# ShiftReg.net
KiCad netlist of a schematic drawn in EAGLE
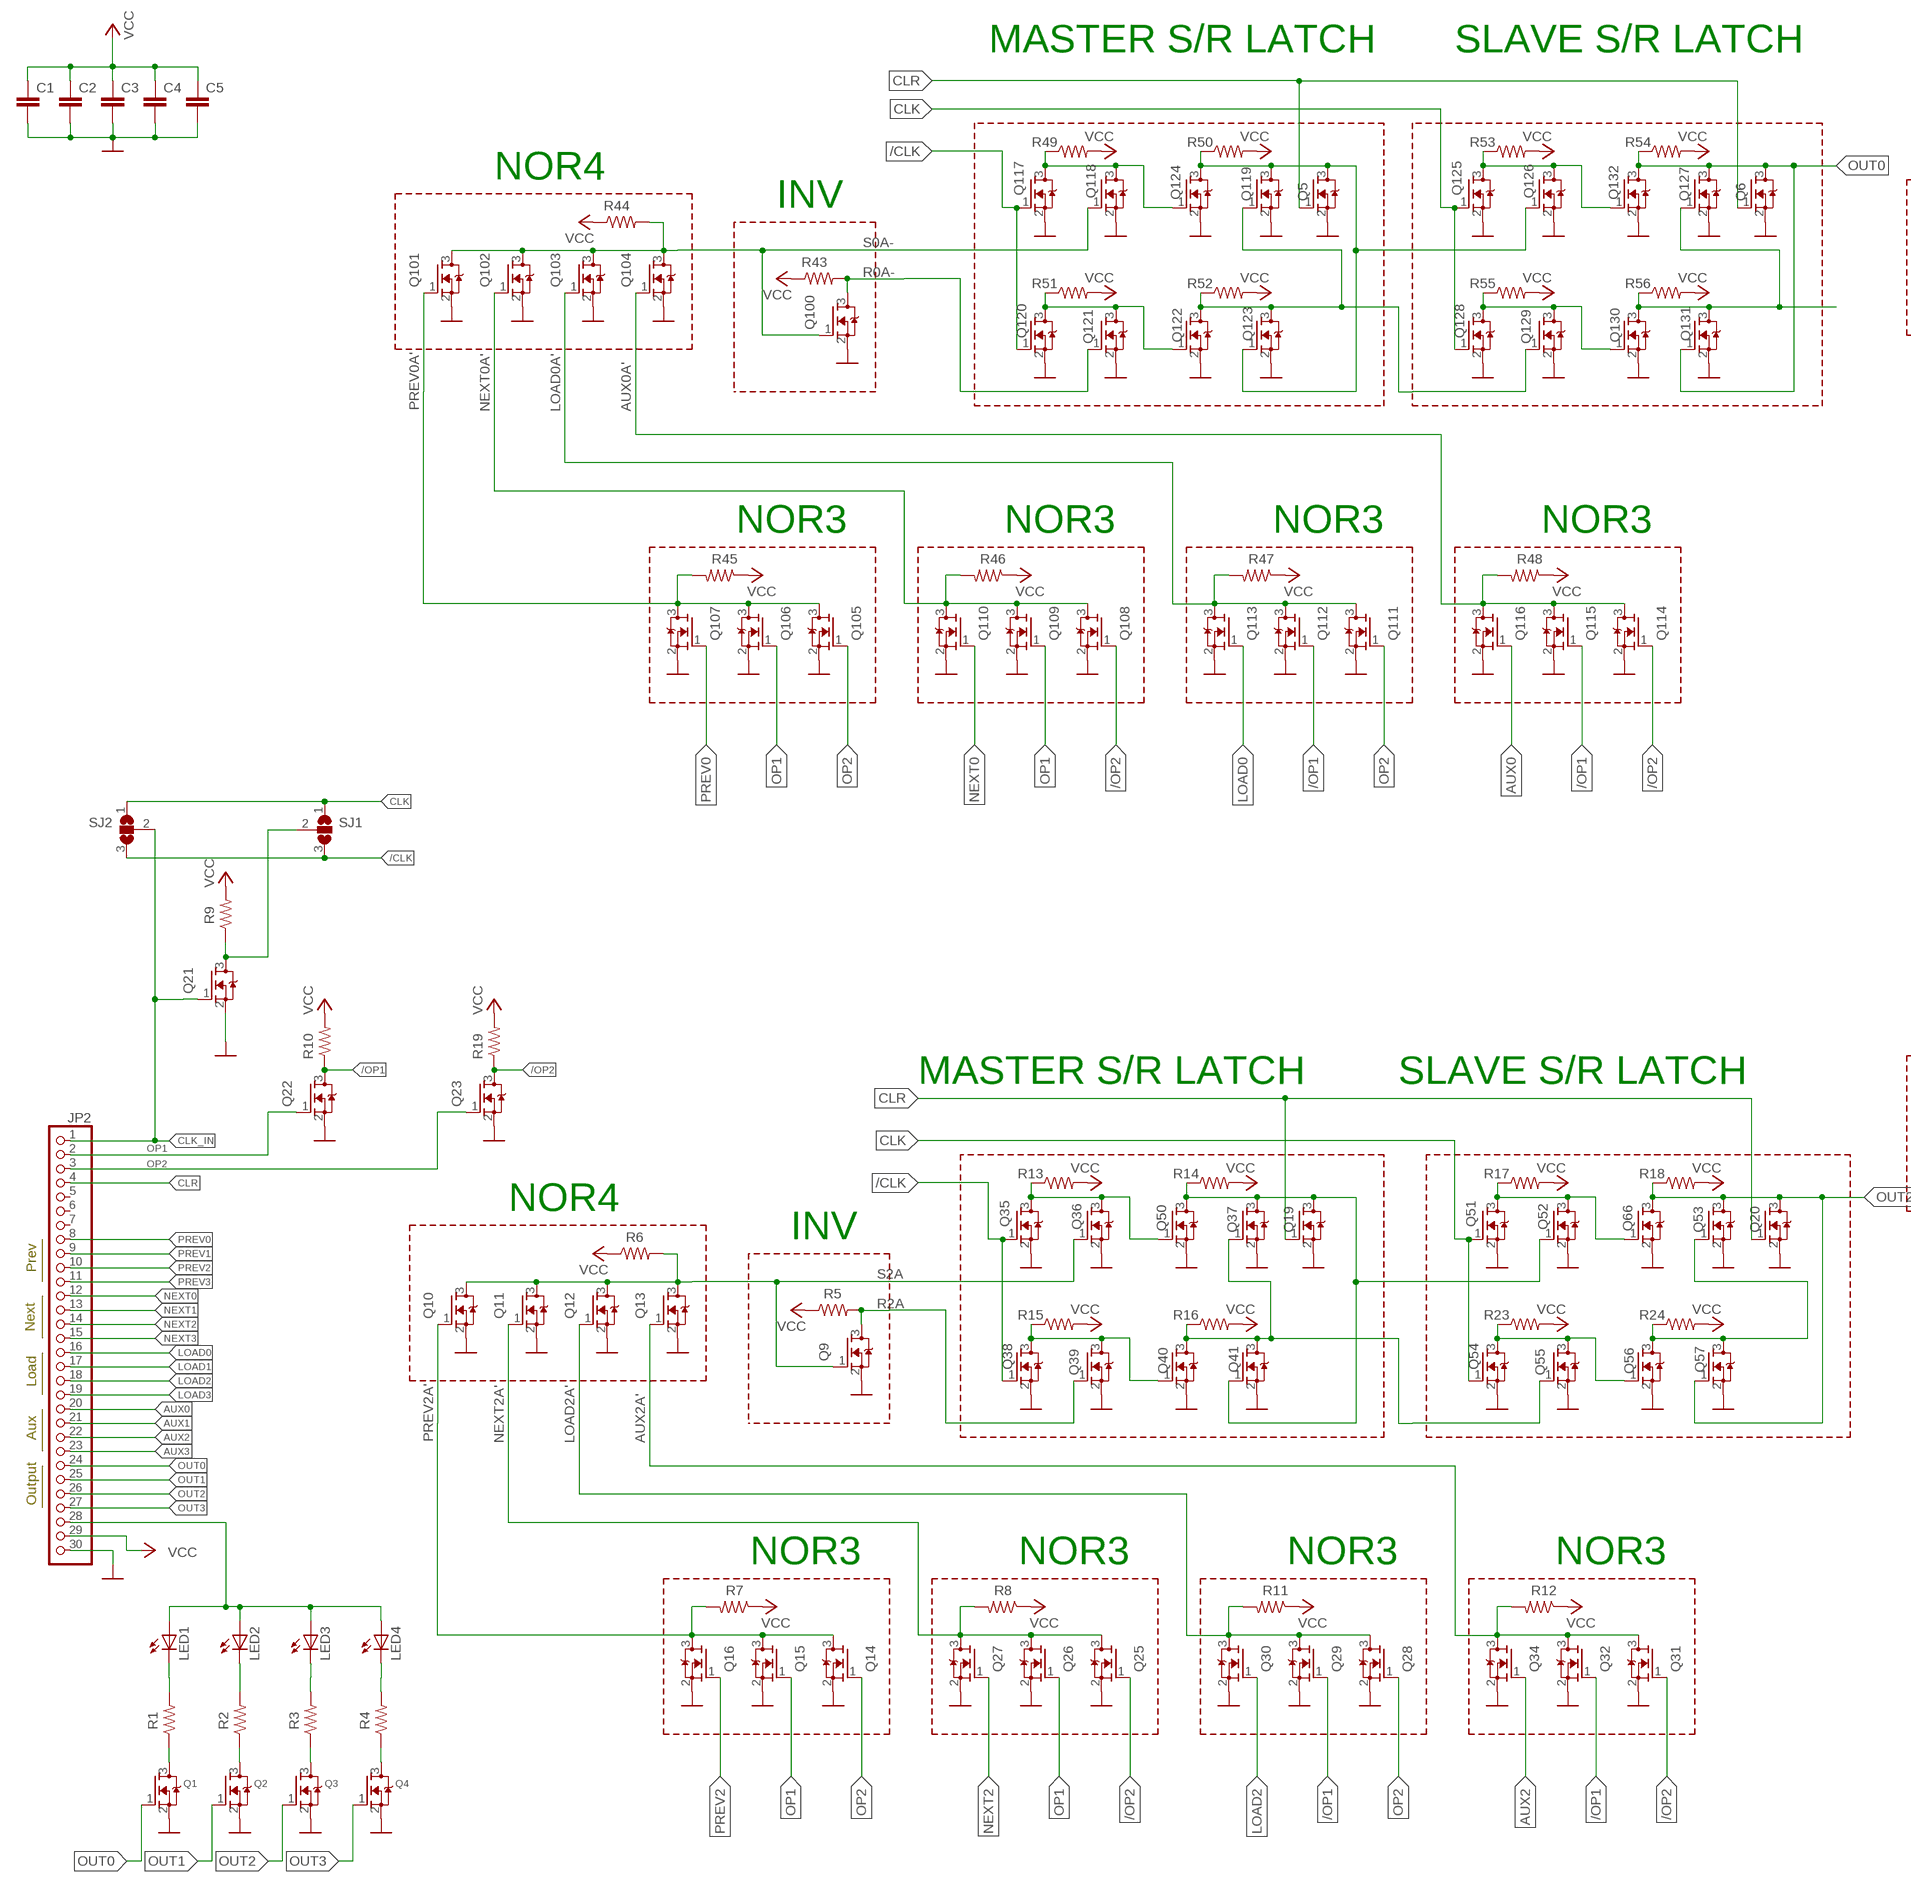
[diagram p0: schematic, sheet 1, part 1 of 2]
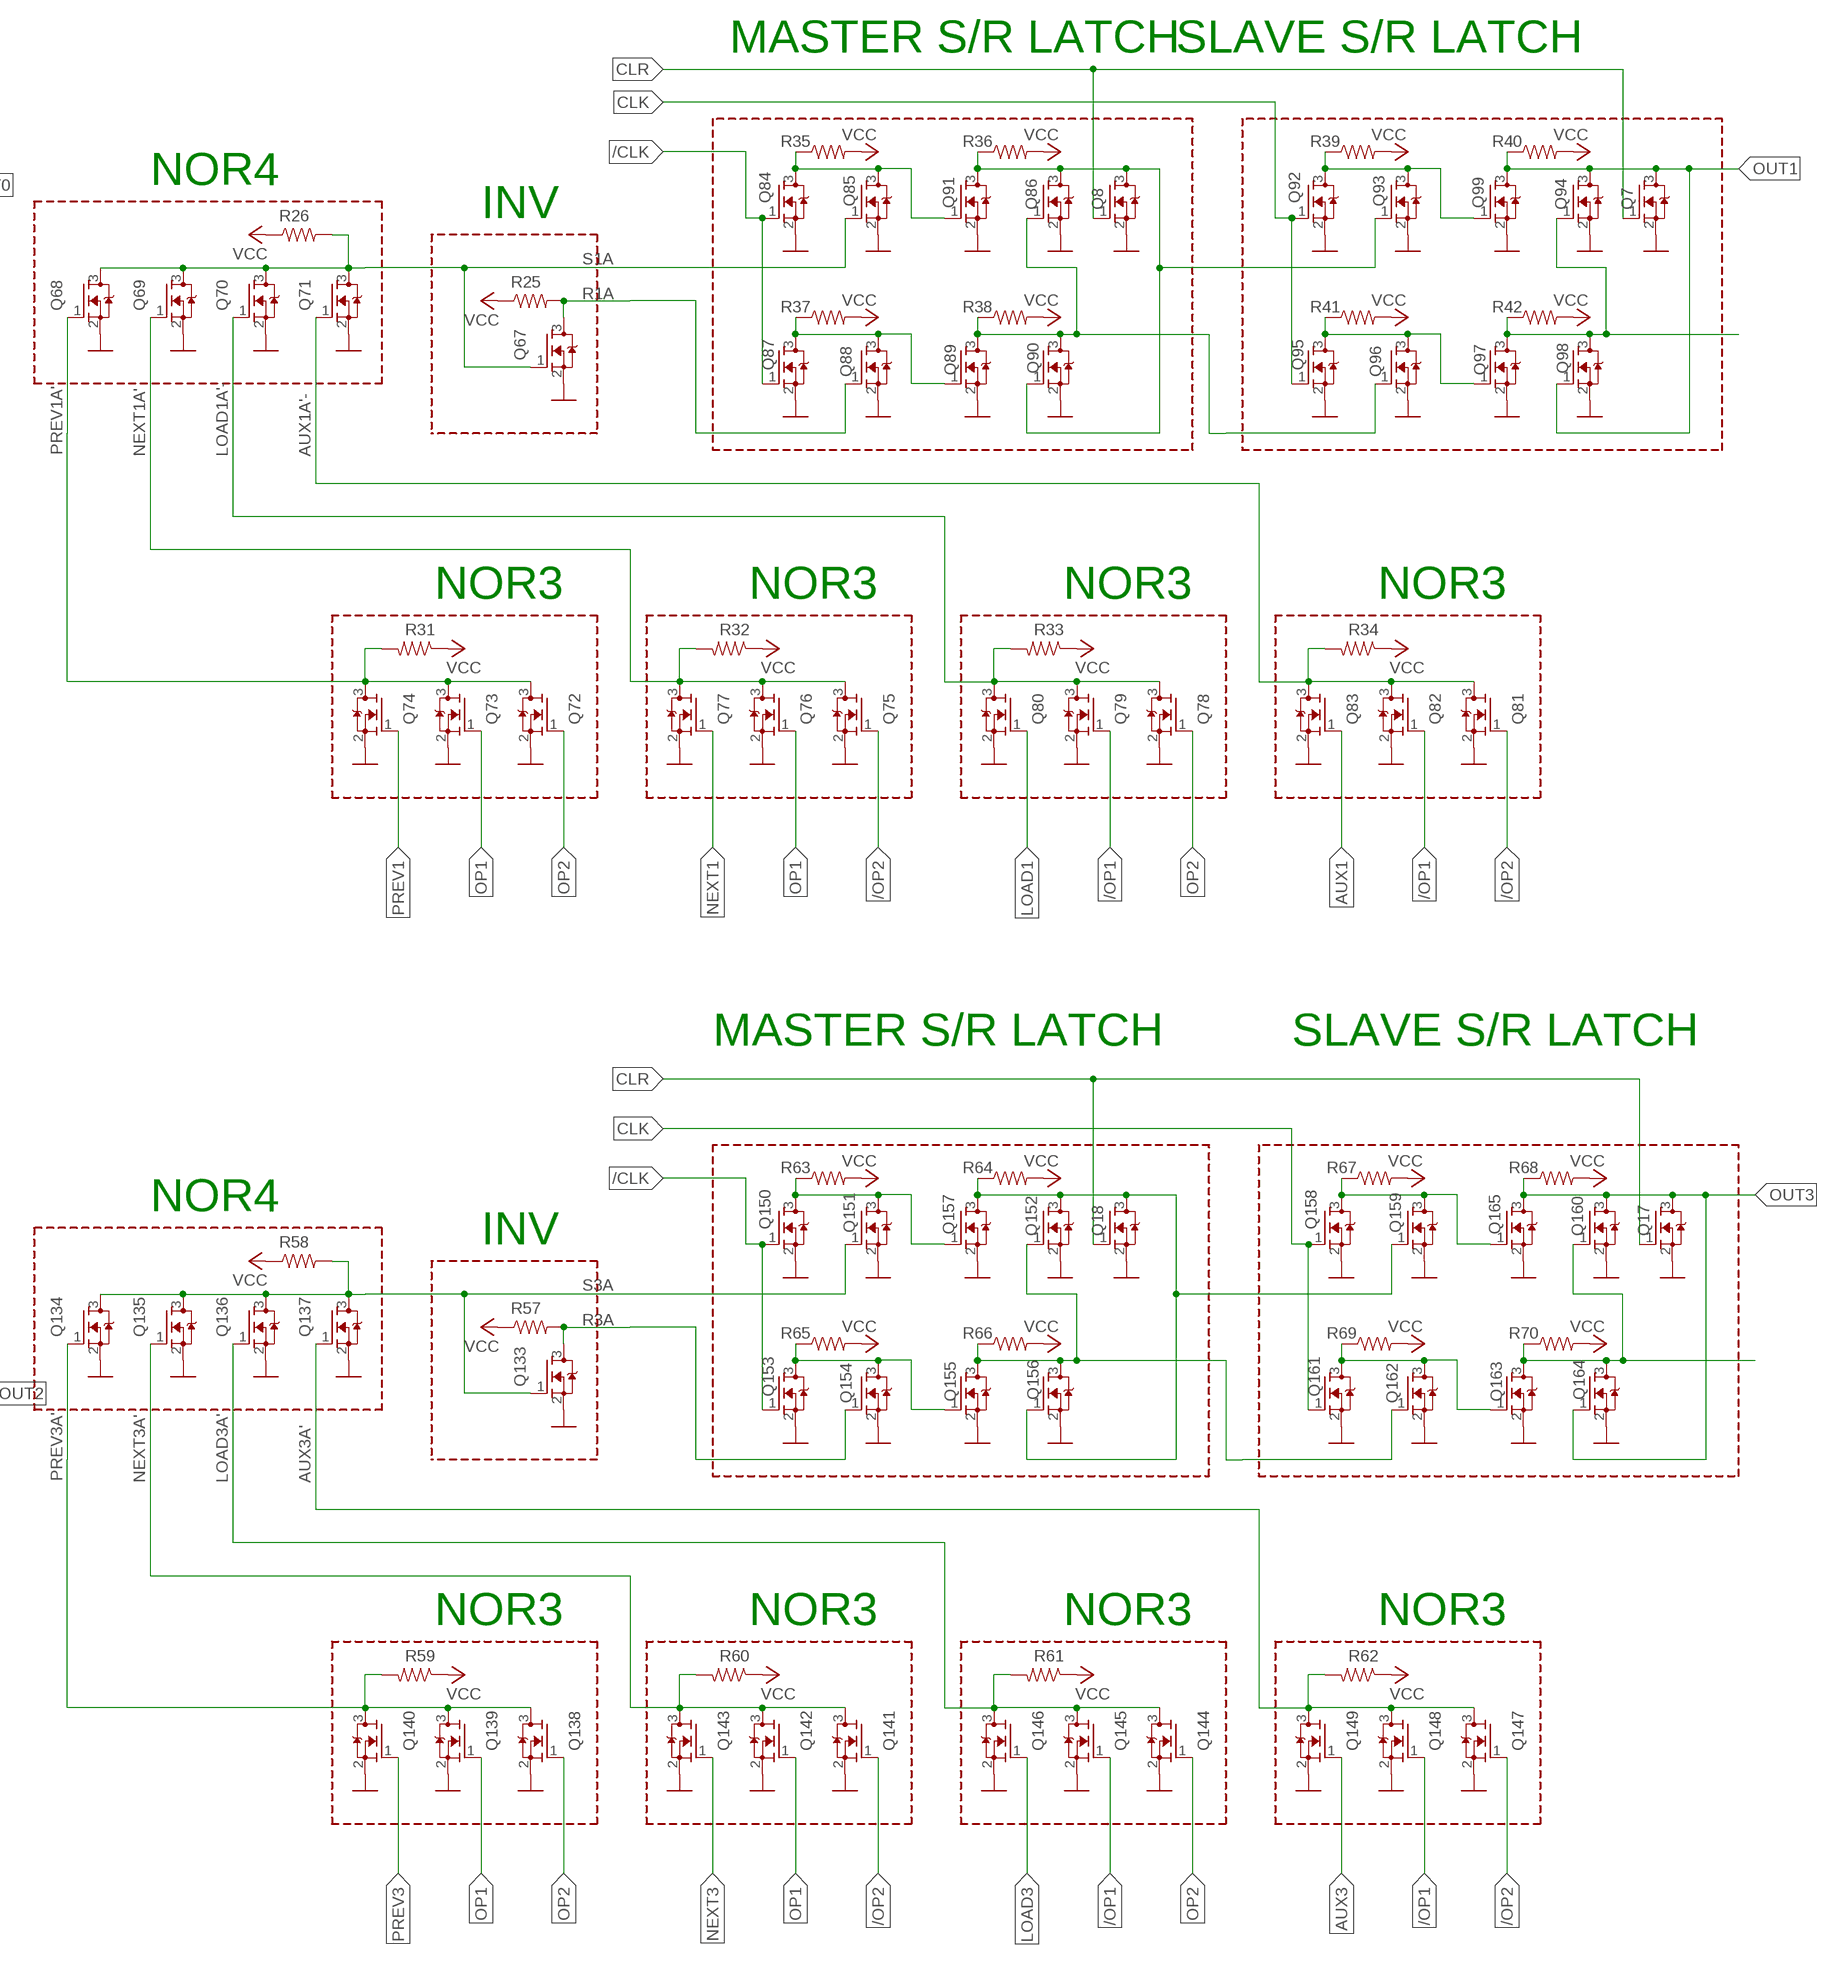
[diagram p1: schematic, sheet 1, part 2 of 2]

(export (version "E")
  (design (tool "Eeschema 10.0.6"))
  (components
    (comp (ref "C1")
      (value "C-EUC0805K")
      (footprint "eagle-import:C0805K")
      (libsource (lib "eagle-import") (part "C-EUC0805K"))
    )
    (comp (ref "C2")
      (value "C-EUC0805K")
      (footprint "eagle-import:C0805K")
      (libsource (lib "eagle-import") (part "C-EUC0805K"))
    )
    (comp (ref "C3")
      (value "C-EUC0805K")
      (footprint "eagle-import:C0805K")
      (libsource (lib "eagle-import") (part "C-EUC0805K"))
    )
    (comp (ref "C4")
      (value "C-EUC0805K")
      (footprint "eagle-import:C0805K")
      (libsource (lib "eagle-import") (part "C-EUC0805K"))
    )
    (comp (ref "C5")
      (value "C-EUC0805K")
      (footprint "eagle-import:C0805K")
      (libsource (lib "eagle-import") (part "C-EUC0805K"))
    )
    (comp (ref "JP2")
      (value "PINHD-1X30")
      (footprint "eagle-import:1X30")
      (libsource (lib "eagle-import") (part "PINHD-1X30"))
    )
    (comp (ref "LED1")
      (value "LEDSQR2X5")
      (footprint "eagle-import:LED2X5")
      (libsource (lib "eagle-import") (part "LEDSQR2X5"))
    )
    (comp (ref "LED2")
      (value "LEDSQR2X5")
      (footprint "eagle-import:LED2X5")
      (libsource (lib "eagle-import") (part "LEDSQR2X5"))
    )
    (comp (ref "LED3")
      (value "LEDSQR2X5")
      (footprint "eagle-import:LED2X5")
      (libsource (lib "eagle-import") (part "LEDSQR2X5"))
    )
    (comp (ref "LED4")
      (value "LEDSQR2X5")
      (footprint "eagle-import:LED2X5")
      (libsource (lib "eagle-import") (part "LEDSQR2X5"))
    )
    (comp (ref "Q1")
      (value "NMOSREFLOW")
      (footprint "eagle-import:SOT23")
      (libsource (lib "eagle-import") (part "NMOSREFLOW"))
    )
    (comp (ref "Q2")
      (value "NMOSREFLOW")
      (footprint "eagle-import:SOT23")
      (libsource (lib "eagle-import") (part "NMOSREFLOW"))
    )
    (comp (ref "Q3")
      (value "NMOSREFLOW")
      (footprint "eagle-import:SOT23")
      (libsource (lib "eagle-import") (part "NMOSREFLOW"))
    )
    (comp (ref "Q4")
      (value "NMOSREFLOW")
      (footprint "eagle-import:SOT23")
      (libsource (lib "eagle-import") (part "NMOSREFLOW"))
    )
    (comp (ref "Q5")
      (value "310mA/60V/1.6Ω")
      (footprint "eagle-import:SOT23")
      (libsource (lib "eagle-import") (part "NMOSREFLOW"))
    )
    (comp (ref "Q6")
      (value "310mA/60V/1.6Ω")
      (footprint "eagle-import:SOT23")
      (libsource (lib "eagle-import") (part "NMOSREFLOW"))
    )
    (comp (ref "Q7")
      (value "310mA/60V/1.6Ω")
      (footprint "eagle-import:SOT23")
      (libsource (lib "eagle-import") (part "NMOSREFLOW"))
    )
    (comp (ref "Q8")
      (value "310mA/60V/1.6Ω")
      (footprint "eagle-import:SOT23")
      (libsource (lib "eagle-import") (part "NMOSREFLOW"))
    )
    (comp (ref "Q9")
      (value "310mA/60V/1.6Ω")
      (footprint "eagle-import:SOT23")
      (libsource (lib "eagle-import") (part "NMOSREFLOW"))
    )
    (comp (ref "Q10")
      (value "310mA/60V/1.6Ω")
      (footprint "eagle-import:SOT23")
      (libsource (lib "eagle-import") (part "NMOSREFLOW"))
    )
    (comp (ref "Q11")
      (value "310mA/60V/1.6Ω")
      (footprint "eagle-import:SOT23")
      (libsource (lib "eagle-import") (part "NMOSREFLOW"))
    )
    (comp (ref "Q12")
      (value "310mA/60V/1.6Ω")
      (footprint "eagle-import:SOT23")
      (libsource (lib "eagle-import") (part "NMOSREFLOW"))
    )
    (comp (ref "Q13")
      (value "310mA/60V/1.6Ω")
      (footprint "eagle-import:SOT23")
      (libsource (lib "eagle-import") (part "NMOSREFLOW"))
    )
    (comp (ref "Q14")
      (value "310mA/60V/1.6Ω")
      (footprint "eagle-import:SOT23")
      (libsource (lib "eagle-import") (part "NMOSREFLOW"))
    )
    (comp (ref "Q15")
      (value "310mA/60V/1.6Ω")
      (footprint "eagle-import:SOT23")
      (libsource (lib "eagle-import") (part "NMOSREFLOW"))
    )
    (comp (ref "Q16")
      (value "310mA/60V/1.6Ω")
      (footprint "eagle-import:SOT23")
      (libsource (lib "eagle-import") (part "NMOSREFLOW"))
    )
    (comp (ref "Q17")
      (value "310mA/60V/1.6Ω")
      (footprint "eagle-import:SOT23")
      (libsource (lib "eagle-import") (part "NMOSREFLOW"))
    )
    (comp (ref "Q18")
      (value "310mA/60V/1.6Ω")
      (footprint "eagle-import:SOT23")
      (libsource (lib "eagle-import") (part "NMOSREFLOW"))
    )
    (comp (ref "Q19")
      (value "310mA/60V/1.6Ω")
      (footprint "eagle-import:SOT23")
      (libsource (lib "eagle-import") (part "NMOSREFLOW"))
    )
    (comp (ref "Q20")
      (value "310mA/60V/1.6Ω")
      (footprint "eagle-import:SOT23")
      (libsource (lib "eagle-import") (part "NMOSREFLOW"))
    )
    (comp (ref "Q21")
      (value "310mA/60V/1.6Ω")
      (footprint "eagle-import:SOT23")
      (libsource (lib "eagle-import") (part "NMOSREFLOW"))
    )
    (comp (ref "Q22")
      (value "310mA/60V/1.6Ω")
      (footprint "eagle-import:SOT23")
      (libsource (lib "eagle-import") (part "NMOSREFLOW"))
    )
    (comp (ref "Q23")
      (value "310mA/60V/1.6Ω")
      (footprint "eagle-import:SOT23")
      (libsource (lib "eagle-import") (part "NMOSREFLOW"))
    )
    (comp (ref "Q25")
      (value "310mA/60V/1.6Ω")
      (footprint "eagle-import:SOT23")
      (libsource (lib "eagle-import") (part "NMOSREFLOW"))
    )
    (comp (ref "Q26")
      (value "310mA/60V/1.6Ω")
      (footprint "eagle-import:SOT23")
      (libsource (lib "eagle-import") (part "NMOSREFLOW"))
    )
    (comp (ref "Q27")
      (value "310mA/60V/1.6Ω")
      (footprint "eagle-import:SOT23")
      (libsource (lib "eagle-import") (part "NMOSREFLOW"))
    )
    (comp (ref "Q28")
      (value "310mA/60V/1.6Ω")
      (footprint "eagle-import:SOT23")
      (libsource (lib "eagle-import") (part "NMOSREFLOW"))
    )
    (comp (ref "Q29")
      (value "310mA/60V/1.6Ω")
      (footprint "eagle-import:SOT23")
      (libsource (lib "eagle-import") (part "NMOSREFLOW"))
    )
    (comp (ref "Q30")
      (value "310mA/60V/1.6Ω")
      (footprint "eagle-import:SOT23")
      (libsource (lib "eagle-import") (part "NMOSREFLOW"))
    )
    (comp (ref "Q31")
      (value "310mA/60V/1.6Ω")
      (footprint "eagle-import:SOT23")
      (libsource (lib "eagle-import") (part "NMOSREFLOW"))
    )
    (comp (ref "Q32")
      (value "310mA/60V/1.6Ω")
      (footprint "eagle-import:SOT23")
      (libsource (lib "eagle-import") (part "NMOSREFLOW"))
    )
    (comp (ref "Q34")
      (value "310mA/60V/1.6Ω")
      (footprint "eagle-import:SOT23")
      (libsource (lib "eagle-import") (part "NMOSREFLOW"))
    )
    (comp (ref "Q35")
      (value "310mA/60V/1.6Ω")
      (footprint "eagle-import:SOT23")
      (fields (field (name "SPICEPREFIX") "M"))
      (libsource (lib "eagle-import") (part "NMOSREFLOW"))
    )
    (comp (ref "Q36")
      (value "310mA/60V/1.6Ω")
      (footprint "eagle-import:SOT23")
      (libsource (lib "eagle-import") (part "NMOSREFLOW"))
    )
    (comp (ref "Q37")
      (value "310mA/60V/1.6Ω")
      (footprint "eagle-import:SOT23")
      (libsource (lib "eagle-import") (part "NMOSREFLOW"))
    )
    (comp (ref "Q38")
      (value "310mA/60V/1.6Ω")
      (footprint "eagle-import:SOT23")
      (libsource (lib "eagle-import") (part "NMOSREFLOW"))
    )
    (comp (ref "Q39")
      (value "310mA/60V/1.6Ω")
      (footprint "eagle-import:SOT23")
      (libsource (lib "eagle-import") (part "NMOSREFLOW"))
    )
    (comp (ref "Q40")
      (value "310mA/60V/1.6Ω")
      (footprint "eagle-import:SOT23")
      (libsource (lib "eagle-import") (part "NMOSREFLOW"))
    )
    (comp (ref "Q41")
      (value "310mA/60V/1.6Ω")
      (footprint "eagle-import:SOT23")
      (libsource (lib "eagle-import") (part "NMOSREFLOW"))
    )
    (comp (ref "Q50")
      (value "310mA/60V/1.6Ω")
      (footprint "eagle-import:SOT23")
      (fields (field (name "SPICEPREFIX") "M"))
      (libsource (lib "eagle-import") (part "NMOSREFLOW"))
    )
    (comp (ref "Q51")
      (value "310mA/60V/1.6Ω")
      (footprint "eagle-import:SOT23")
      (fields (field (name "SPICEPREFIX") "M"))
      (libsource (lib "eagle-import") (part "NMOSREFLOW"))
    )
    (comp (ref "Q52")
      (value "310mA/60V/1.6Ω")
      (footprint "eagle-import:SOT23")
      (libsource (lib "eagle-import") (part "NMOSREFLOW"))
    )
    (comp (ref "Q53")
      (value "310mA/60V/1.6Ω")
      (footprint "eagle-import:SOT23")
      (libsource (lib "eagle-import") (part "NMOSREFLOW"))
    )
    (comp (ref "Q54")
      (value "310mA/60V/1.6Ω")
      (footprint "eagle-import:SOT23")
      (libsource (lib "eagle-import") (part "NMOSREFLOW"))
    )
    (comp (ref "Q55")
      (value "310mA/60V/1.6Ω")
      (footprint "eagle-import:SOT23")
      (libsource (lib "eagle-import") (part "NMOSREFLOW"))
    )
    (comp (ref "Q56")
      (value "310mA/60V/1.6Ω")
      (footprint "eagle-import:SOT23")
      (libsource (lib "eagle-import") (part "NMOSREFLOW"))
    )
    (comp (ref "Q57")
      (value "310mA/60V/1.6Ω")
      (footprint "eagle-import:SOT23")
      (libsource (lib "eagle-import") (part "NMOSREFLOW"))
    )
    (comp (ref "Q66")
      (value "310mA/60V/1.6Ω")
      (footprint "eagle-import:SOT23")
      (fields (field (name "SPICEPREFIX") "M"))
      (libsource (lib "eagle-import") (part "NMOSREFLOW"))
    )
    (comp (ref "Q67")
      (value "310mA/60V/1.6Ω")
      (footprint "eagle-import:SOT23")
      (libsource (lib "eagle-import") (part "NMOSREFLOW"))
    )
    (comp (ref "Q68")
      (value "310mA/60V/1.6Ω")
      (footprint "eagle-import:SOT23")
      (libsource (lib "eagle-import") (part "NMOSREFLOW"))
    )
    (comp (ref "Q69")
      (value "310mA/60V/1.6Ω")
      (footprint "eagle-import:SOT23")
      (libsource (lib "eagle-import") (part "NMOSREFLOW"))
    )
    (comp (ref "Q70")
      (value "310mA/60V/1.6Ω")
      (footprint "eagle-import:SOT23")
      (libsource (lib "eagle-import") (part "NMOSREFLOW"))
    )
    (comp (ref "Q71")
      (value "310mA/60V/1.6Ω")
      (footprint "eagle-import:SOT23")
      (libsource (lib "eagle-import") (part "NMOSREFLOW"))
    )
    (comp (ref "Q72")
      (value "310mA/60V/1.6Ω")
      (footprint "eagle-import:SOT23")
      (libsource (lib "eagle-import") (part "NMOSREFLOW"))
    )
    (comp (ref "Q73")
      (value "310mA/60V/1.6Ω")
      (footprint "eagle-import:SOT23")
      (libsource (lib "eagle-import") (part "NMOSREFLOW"))
    )
    (comp (ref "Q74")
      (value "310mA/60V/1.6Ω")
      (footprint "eagle-import:SOT23")
      (libsource (lib "eagle-import") (part "NMOSREFLOW"))
    )
    (comp (ref "Q75")
      (value "310mA/60V/1.6Ω")
      (footprint "eagle-import:SOT23")
      (libsource (lib "eagle-import") (part "NMOSREFLOW"))
    )
    (comp (ref "Q76")
      (value "310mA/60V/1.6Ω")
      (footprint "eagle-import:SOT23")
      (libsource (lib "eagle-import") (part "NMOSREFLOW"))
    )
    (comp (ref "Q77")
      (value "310mA/60V/1.6Ω")
      (footprint "eagle-import:SOT23")
      (libsource (lib "eagle-import") (part "NMOSREFLOW"))
    )
    (comp (ref "Q78")
      (value "310mA/60V/1.6Ω")
      (footprint "eagle-import:SOT23")
      (libsource (lib "eagle-import") (part "NMOSREFLOW"))
    )
    (comp (ref "Q79")
      (value "310mA/60V/1.6Ω")
      (footprint "eagle-import:SOT23")
      (libsource (lib "eagle-import") (part "NMOSREFLOW"))
    )
    (comp (ref "Q80")
      (value "310mA/60V/1.6Ω")
      (footprint "eagle-import:SOT23")
      (libsource (lib "eagle-import") (part "NMOSREFLOW"))
    )
    (comp (ref "Q81")
      (value "310mA/60V/1.6Ω")
      (footprint "eagle-import:SOT23")
      (libsource (lib "eagle-import") (part "NMOSREFLOW"))
    )
    (comp (ref "Q82")
      (value "310mA/60V/1.6Ω")
      (footprint "eagle-import:SOT23")
      (libsource (lib "eagle-import") (part "NMOSREFLOW"))
    )
    (comp (ref "Q83")
      (value "310mA/60V/1.6Ω")
      (footprint "eagle-import:SOT23")
      (libsource (lib "eagle-import") (part "NMOSREFLOW"))
    )
    (comp (ref "Q84")
      (value "310mA/60V/1.6Ω")
      (footprint "eagle-import:SOT23")
      (fields (field (name "SPICEPREFIX") "M"))
      (libsource (lib "eagle-import") (part "NMOSREFLOW"))
    )
    (comp (ref "Q85")
      (value "310mA/60V/1.6Ω")
      (footprint "eagle-import:SOT23")
      (libsource (lib "eagle-import") (part "NMOSREFLOW"))
    )
    (comp (ref "Q86")
      (value "310mA/60V/1.6Ω")
      (footprint "eagle-import:SOT23")
      (libsource (lib "eagle-import") (part "NMOSREFLOW"))
    )
    (comp (ref "Q87")
      (value "310mA/60V/1.6Ω")
      (footprint "eagle-import:SOT23")
      (libsource (lib "eagle-import") (part "NMOSREFLOW"))
    )
    (comp (ref "Q88")
      (value "310mA/60V/1.6Ω")
      (footprint "eagle-import:SOT23")
      (libsource (lib "eagle-import") (part "NMOSREFLOW"))
    )
    (comp (ref "Q89")
      (value "310mA/60V/1.6Ω")
      (footprint "eagle-import:SOT23")
      (libsource (lib "eagle-import") (part "NMOSREFLOW"))
    )
    (comp (ref "Q90")
      (value "310mA/60V/1.6Ω")
      (footprint "eagle-import:SOT23")
      (libsource (lib "eagle-import") (part "NMOSREFLOW"))
    )
    (comp (ref "Q91")
      (value "310mA/60V/1.6Ω")
      (footprint "eagle-import:SOT23")
      (fields (field (name "SPICEPREFIX") "M"))
      (libsource (lib "eagle-import") (part "NMOSREFLOW"))
    )
    (comp (ref "Q92")
      (value "310mA/60V/1.6Ω")
      (footprint "eagle-import:SOT23")
      (fields (field (name "SPICEPREFIX") "M"))
      (libsource (lib "eagle-import") (part "NMOSREFLOW"))
    )
    (comp (ref "Q93")
      (value "310mA/60V/1.6Ω")
      (footprint "eagle-import:SOT23")
      (libsource (lib "eagle-import") (part "NMOSREFLOW"))
    )
    (comp (ref "Q94")
      (value "310mA/60V/1.6Ω")
      (footprint "eagle-import:SOT23")
      (libsource (lib "eagle-import") (part "NMOSREFLOW"))
    )
    (comp (ref "Q95")
      (value "310mA/60V/1.6Ω")
      (footprint "eagle-import:SOT23")
      (libsource (lib "eagle-import") (part "NMOSREFLOW"))
    )
    (comp (ref "Q96")
      (value "310mA/60V/1.6Ω")
      (footprint "eagle-import:SOT23")
      (libsource (lib "eagle-import") (part "NMOSREFLOW"))
    )
    (comp (ref "Q97")
      (value "310mA/60V/1.6Ω")
      (footprint "eagle-import:SOT23")
      (libsource (lib "eagle-import") (part "NMOSREFLOW"))
    )
    (comp (ref "Q98")
      (value "310mA/60V/1.6Ω")
      (footprint "eagle-import:SOT23")
      (libsource (lib "eagle-import") (part "NMOSREFLOW"))
    )
    (comp (ref "Q99")
      (value "310mA/60V/1.6Ω")
      (footprint "eagle-import:SOT23")
      (fields (field (name "SPICEPREFIX") "M"))
      (libsource (lib "eagle-import") (part "NMOSREFLOW"))
    )
    (comp (ref "Q100")
      (value "310mA/60V/1.6Ω")
      (footprint "eagle-import:SOT23")
      (libsource (lib "eagle-import") (part "NMOSREFLOW"))
    )
    (comp (ref "Q101")
      (value "310mA/60V/1.6Ω")
      (footprint "eagle-import:SOT23")
      (libsource (lib "eagle-import") (part "NMOSREFLOW"))
    )
    (comp (ref "Q102")
      (value "310mA/60V/1.6Ω")
      (footprint "eagle-import:SOT23")
      (libsource (lib "eagle-import") (part "NMOSREFLOW"))
    )
    (comp (ref "Q103")
      (value "310mA/60V/1.6Ω")
      (footprint "eagle-import:SOT23")
      (libsource (lib "eagle-import") (part "NMOSREFLOW"))
    )
    (comp (ref "Q104")
      (value "310mA/60V/1.6Ω")
      (footprint "eagle-import:SOT23")
      (libsource (lib "eagle-import") (part "NMOSREFLOW"))
    )
    (comp (ref "Q105")
      (value "310mA/60V/1.6Ω")
      (footprint "eagle-import:SOT23")
      (libsource (lib "eagle-import") (part "NMOSREFLOW"))
    )
    (comp (ref "Q106")
      (value "310mA/60V/1.6Ω")
      (footprint "eagle-import:SOT23")
      (libsource (lib "eagle-import") (part "NMOSREFLOW"))
    )
    (comp (ref "Q107")
      (value "310mA/60V/1.6Ω")
      (footprint "eagle-import:SOT23")
      (libsource (lib "eagle-import") (part "NMOSREFLOW"))
    )
    (comp (ref "Q108")
      (value "310mA/60V/1.6Ω")
      (footprint "eagle-import:SOT23")
      (libsource (lib "eagle-import") (part "NMOSREFLOW"))
    )
    (comp (ref "Q109")
      (value "310mA/60V/1.6Ω")
      (footprint "eagle-import:SOT23")
      (libsource (lib "eagle-import") (part "NMOSREFLOW"))
    )
    (comp (ref "Q110")
      (value "310mA/60V/1.6Ω")
      (footprint "eagle-import:SOT23")
      (libsource (lib "eagle-import") (part "NMOSREFLOW"))
    )
    (comp (ref "Q111")
      (value "310mA/60V/1.6Ω")
      (footprint "eagle-import:SOT23")
      (libsource (lib "eagle-import") (part "NMOSREFLOW"))
    )
    (comp (ref "Q112")
      (value "310mA/60V/1.6Ω")
      (footprint "eagle-import:SOT23")
      (libsource (lib "eagle-import") (part "NMOSREFLOW"))
    )
    (comp (ref "Q113")
      (value "310mA/60V/1.6Ω")
      (footprint "eagle-import:SOT23")
      (libsource (lib "eagle-import") (part "NMOSREFLOW"))
    )
    (comp (ref "Q114")
      (value "310mA/60V/1.6Ω")
      (footprint "eagle-import:SOT23")
      (libsource (lib "eagle-import") (part "NMOSREFLOW"))
    )
    (comp (ref "Q115")
      (value "310mA/60V/1.6Ω")
      (footprint "eagle-import:SOT23")
      (libsource (lib "eagle-import") (part "NMOSREFLOW"))
    )
    (comp (ref "Q116")
      (value "310mA/60V/1.6Ω")
      (footprint "eagle-import:SOT23")
      (libsource (lib "eagle-import") (part "NMOSREFLOW"))
    )
    (comp (ref "Q117")
      (value "310mA/60V/1.6Ω")
      (footprint "eagle-import:SOT23")
      (fields (field (name "SPICEPREFIX") "M"))
      (libsource (lib "eagle-import") (part "NMOSREFLOW"))
    )
    (comp (ref "Q118")
      (value "310mA/60V/1.6Ω")
      (footprint "eagle-import:SOT23")
      (libsource (lib "eagle-import") (part "NMOSREFLOW"))
    )
    (comp (ref "Q119")
      (value "310mA/60V/1.6Ω")
      (footprint "eagle-import:SOT23")
      (libsource (lib "eagle-import") (part "NMOSREFLOW"))
    )
    (comp (ref "Q120")
      (value "310mA/60V/1.6Ω")
      (footprint "eagle-import:SOT23")
      (libsource (lib "eagle-import") (part "NMOSREFLOW"))
    )
    (comp (ref "Q121")
      (value "310mA/60V/1.6Ω")
      (footprint "eagle-import:SOT23")
      (libsource (lib "eagle-import") (part "NMOSREFLOW"))
    )
    (comp (ref "Q122")
      (value "310mA/60V/1.6Ω")
      (footprint "eagle-import:SOT23")
      (libsource (lib "eagle-import") (part "NMOSREFLOW"))
    )
    (comp (ref "Q123")
      (value "310mA/60V/1.6Ω")
      (footprint "eagle-import:SOT23")
      (libsource (lib "eagle-import") (part "NMOSREFLOW"))
    )
    (comp (ref "Q124")
      (value "310mA/60V/1.6Ω")
      (footprint "eagle-import:SOT23")
      (fields (field (name "SPICEPREFIX") "M"))
      (libsource (lib "eagle-import") (part "NMOSREFLOW"))
    )
    (comp (ref "Q125")
      (value "310mA/60V/1.6Ω")
      (footprint "eagle-import:SOT23")
      (fields (field (name "SPICEPREFIX") "M"))
      (libsource (lib "eagle-import") (part "NMOSREFLOW"))
    )
    (comp (ref "Q126")
      (value "310mA/60V/1.6Ω")
      (footprint "eagle-import:SOT23")
      (libsource (lib "eagle-import") (part "NMOSREFLOW"))
    )
    (comp (ref "Q127")
      (value "310mA/60V/1.6Ω")
      (footprint "eagle-import:SOT23")
      (libsource (lib "eagle-import") (part "NMOSREFLOW"))
    )
    (comp (ref "Q128")
      (value "310mA/60V/1.6Ω")
      (footprint "eagle-import:SOT23")
      (libsource (lib "eagle-import") (part "NMOSREFLOW"))
    )
    (comp (ref "Q129")
      (value "310mA/60V/1.6Ω")
      (footprint "eagle-import:SOT23")
      (libsource (lib "eagle-import") (part "NMOSREFLOW"))
    )
    (comp (ref "Q130")
      (value "310mA/60V/1.6Ω")
      (footprint "eagle-import:SOT23")
      (libsource (lib "eagle-import") (part "NMOSREFLOW"))
    )
    (comp (ref "Q131")
      (value "310mA/60V/1.6Ω")
      (footprint "eagle-import:SOT23")
      (libsource (lib "eagle-import") (part "NMOSREFLOW"))
    )
    (comp (ref "Q132")
      (value "310mA/60V/1.6Ω")
      (footprint "eagle-import:SOT23")
      (fields (field (name "SPICEPREFIX") "M"))
      (libsource (lib "eagle-import") (part "NMOSREFLOW"))
    )
    (comp (ref "Q133")
      (value "310mA/60V/1.6Ω")
      (footprint "eagle-import:SOT23")
      (libsource (lib "eagle-import") (part "NMOSREFLOW"))
    )
    (comp (ref "Q134")
      (value "310mA/60V/1.6Ω")
      (footprint "eagle-import:SOT23")
      (libsource (lib "eagle-import") (part "NMOSREFLOW"))
    )
    (comp (ref "Q135")
      (value "310mA/60V/1.6Ω")
      (footprint "eagle-import:SOT23")
      (libsource (lib "eagle-import") (part "NMOSREFLOW"))
    )
    (comp (ref "Q136")
      (value "310mA/60V/1.6Ω")
      (footprint "eagle-import:SOT23")
      (libsource (lib "eagle-import") (part "NMOSREFLOW"))
    )
    (comp (ref "Q137")
      (value "310mA/60V/1.6Ω")
      (footprint "eagle-import:SOT23")
      (libsource (lib "eagle-import") (part "NMOSREFLOW"))
    )
    (comp (ref "Q138")
      (value "310mA/60V/1.6Ω")
      (footprint "eagle-import:SOT23")
      (libsource (lib "eagle-import") (part "NMOSREFLOW"))
    )
    (comp (ref "Q139")
      (value "310mA/60V/1.6Ω")
      (footprint "eagle-import:SOT23")
      (libsource (lib "eagle-import") (part "NMOSREFLOW"))
    )
    (comp (ref "Q140")
      (value "310mA/60V/1.6Ω")
      (footprint "eagle-import:SOT23")
      (libsource (lib "eagle-import") (part "NMOSREFLOW"))
    )
    (comp (ref "Q141")
      (value "310mA/60V/1.6Ω")
      (footprint "eagle-import:SOT23")
      (libsource (lib "eagle-import") (part "NMOSREFLOW"))
    )
    (comp (ref "Q142")
      (value "310mA/60V/1.6Ω")
      (footprint "eagle-import:SOT23")
      (libsource (lib "eagle-import") (part "NMOSREFLOW"))
    )
    (comp (ref "Q143")
      (value "310mA/60V/1.6Ω")
      (footprint "eagle-import:SOT23")
      (libsource (lib "eagle-import") (part "NMOSREFLOW"))
    )
    (comp (ref "Q144")
      (value "310mA/60V/1.6Ω")
      (footprint "eagle-import:SOT23")
      (libsource (lib "eagle-import") (part "NMOSREFLOW"))
    )
    (comp (ref "Q145")
      (value "310mA/60V/1.6Ω")
      (footprint "eagle-import:SOT23")
      (libsource (lib "eagle-import") (part "NMOSREFLOW"))
    )
    (comp (ref "Q146")
      (value "310mA/60V/1.6Ω")
      (footprint "eagle-import:SOT23")
      (libsource (lib "eagle-import") (part "NMOSREFLOW"))
    )
    (comp (ref "Q147")
      (value "310mA/60V/1.6Ω")
      (footprint "eagle-import:SOT23")
      (libsource (lib "eagle-import") (part "NMOSREFLOW"))
    )
    (comp (ref "Q148")
      (value "310mA/60V/1.6Ω")
      (footprint "eagle-import:SOT23")
      (libsource (lib "eagle-import") (part "NMOSREFLOW"))
    )
    (comp (ref "Q149")
      (value "310mA/60V/1.6Ω")
      (footprint "eagle-import:SOT23")
      (libsource (lib "eagle-import") (part "NMOSREFLOW"))
    )
    (comp (ref "Q150")
      (value "310mA/60V/1.6Ω")
      (footprint "eagle-import:SOT23")
      (fields (field (name "SPICEPREFIX") "M"))
      (libsource (lib "eagle-import") (part "NMOSREFLOW"))
    )
    (comp (ref "Q151")
      (value "310mA/60V/1.6Ω")
      (footprint "eagle-import:SOT23")
      (libsource (lib "eagle-import") (part "NMOSREFLOW"))
    )
    (comp (ref "Q152")
      (value "310mA/60V/1.6Ω")
      (footprint "eagle-import:SOT23")
      (libsource (lib "eagle-import") (part "NMOSREFLOW"))
    )
    (comp (ref "Q153")
      (value "310mA/60V/1.6Ω")
      (footprint "eagle-import:SOT23")
      (libsource (lib "eagle-import") (part "NMOSREFLOW"))
    )
    (comp (ref "Q154")
      (value "310mA/60V/1.6Ω")
      (footprint "eagle-import:SOT23")
      (libsource (lib "eagle-import") (part "NMOSREFLOW"))
    )
    (comp (ref "Q155")
      (value "310mA/60V/1.6Ω")
      (footprint "eagle-import:SOT23")
      (libsource (lib "eagle-import") (part "NMOSREFLOW"))
    )
    (comp (ref "Q156")
      (value "310mA/60V/1.6Ω")
      (footprint "eagle-import:SOT23")
      (libsource (lib "eagle-import") (part "NMOSREFLOW"))
    )
    (comp (ref "Q157")
      (value "310mA/60V/1.6Ω")
      (footprint "eagle-import:SOT23")
      (fields (field (name "SPICEPREFIX") "M"))
      (libsource (lib "eagle-import") (part "NMOSREFLOW"))
    )
    (comp (ref "Q158")
      (value "310mA/60V/1.6Ω")
      (footprint "eagle-import:SOT23")
      (fields (field (name "SPICEPREFIX") "M"))
      (libsource (lib "eagle-import") (part "NMOSREFLOW"))
    )
    (comp (ref "Q159")
      (value "310mA/60V/1.6Ω")
      (footprint "eagle-import:SOT23")
      (libsource (lib "eagle-import") (part "NMOSREFLOW"))
    )
    (comp (ref "Q160")
      (value "310mA/60V/1.6Ω")
      (footprint "eagle-import:SOT23")
      (libsource (lib "eagle-import") (part "NMOSREFLOW"))
    )
    (comp (ref "Q161")
      (value "310mA/60V/1.6Ω")
      (footprint "eagle-import:SOT23")
      (libsource (lib "eagle-import") (part "NMOSREFLOW"))
    )
    (comp (ref "Q162")
      (value "310mA/60V/1.6Ω")
      (footprint "eagle-import:SOT23")
      (libsource (lib "eagle-import") (part "NMOSREFLOW"))
    )
    (comp (ref "Q163")
      (value "310mA/60V/1.6Ω")
      (footprint "eagle-import:SOT23")
      (libsource (lib "eagle-import") (part "NMOSREFLOW"))
    )
    (comp (ref "Q164")
      (value "310mA/60V/1.6Ω")
      (footprint "eagle-import:SOT23")
      (libsource (lib "eagle-import") (part "NMOSREFLOW"))
    )
    (comp (ref "Q165")
      (value "310mA/60V/1.6Ω")
      (footprint "eagle-import:SOT23")
      (fields (field (name "SPICEPREFIX") "M"))
      (libsource (lib "eagle-import") (part "NMOSREFLOW"))
    )
    (comp (ref "R1")
      (value "RESISTOR0805")
      (footprint "eagle-import:0805")
      (libsource (lib "eagle-import") (part "RESISTOR0805"))
    )
    (comp (ref "R2")
      (value "RESISTOR0805")
      (footprint "eagle-import:0805")
      (libsource (lib "eagle-import") (part "RESISTOR0805"))
    )
    (comp (ref "R3")
      (value "RESISTOR0805")
      (footprint "eagle-import:0805")
      (libsource (lib "eagle-import") (part "RESISTOR0805"))
    )
    (comp (ref "R4")
      (value "RESISTOR0805")
      (footprint "eagle-import:0805")
      (libsource (lib "eagle-import") (part "RESISTOR0805"))
    )
    (comp (ref "R5")
      (value "RESISTOR0805")
      (footprint "eagle-import:0805")
      (libsource (lib "eagle-import") (part "RESISTOR0805"))
    )
    (comp (ref "R6")
      (value "RESISTOR0805")
      (footprint "eagle-import:0805")
      (libsource (lib "eagle-import") (part "RESISTOR0805"))
    )
    (comp (ref "R7")
      (value "RESISTOR0805")
      (footprint "eagle-import:0805")
      (libsource (lib "eagle-import") (part "RESISTOR0805"))
    )
    (comp (ref "R8")
      (value "RESISTOR0805")
      (footprint "eagle-import:0805")
      (libsource (lib "eagle-import") (part "RESISTOR0805"))
    )
    (comp (ref "R9")
      (value "RESISTOR0805")
      (footprint "eagle-import:0805")
      (libsource (lib "eagle-import") (part "RESISTOR0805"))
    )
    (comp (ref "R10")
      (value "RESISTOR0805")
      (footprint "eagle-import:0805")
      (libsource (lib "eagle-import") (part "RESISTOR0805"))
    )
    (comp (ref "R11")
      (value "RESISTOR0805")
      (footprint "eagle-import:0805")
      (libsource (lib "eagle-import") (part "RESISTOR0805"))
    )
    (comp (ref "R12")
      (value "RESISTOR0805")
      (footprint "eagle-import:0805")
      (libsource (lib "eagle-import") (part "RESISTOR0805"))
    )
    (comp (ref "R13")
      (value "RESISTOR0805")
      (footprint "eagle-import:0805")
      (libsource (lib "eagle-import") (part "RESISTOR0805"))
    )
    (comp (ref "R14")
      (value "RESISTOR0805")
      (footprint "eagle-import:0805")
      (libsource (lib "eagle-import") (part "RESISTOR0805"))
    )
    (comp (ref "R15")
      (value "RESISTOR0805")
      (footprint "eagle-import:0805")
      (libsource (lib "eagle-import") (part "RESISTOR0805"))
    )
    (comp (ref "R16")
      (value "RESISTOR0805")
      (footprint "eagle-import:0805")
      (libsource (lib "eagle-import") (part "RESISTOR0805"))
    )
    (comp (ref "R17")
      (value "RESISTOR0805")
      (footprint "eagle-import:0805")
      (libsource (lib "eagle-import") (part "RESISTOR0805"))
    )
    (comp (ref "R18")
      (value "RESISTOR0805")
      (footprint "eagle-import:0805")
      (libsource (lib "eagle-import") (part "RESISTOR0805"))
    )
    (comp (ref "R19")
      (value "RESISTOR0805")
      (footprint "eagle-import:0805")
      (libsource (lib "eagle-import") (part "RESISTOR0805"))
    )
    (comp (ref "R23")
      (value "RESISTOR0805")
      (footprint "eagle-import:0805")
      (libsource (lib "eagle-import") (part "RESISTOR0805"))
    )
    (comp (ref "R24")
      (value "RESISTOR0805")
      (footprint "eagle-import:0805")
      (libsource (lib "eagle-import") (part "RESISTOR0805"))
    )
    (comp (ref "R25")
      (value "RESISTOR0805")
      (footprint "eagle-import:0805")
      (libsource (lib "eagle-import") (part "RESISTOR0805"))
    )
    (comp (ref "R26")
      (value "RESISTOR0805")
      (footprint "eagle-import:0805")
      (libsource (lib "eagle-import") (part "RESISTOR0805"))
    )
    (comp (ref "R31")
      (value "RESISTOR0805")
      (footprint "eagle-import:0805")
      (libsource (lib "eagle-import") (part "RESISTOR0805"))
    )
    (comp (ref "R32")
      (value "RESISTOR0805")
      (footprint "eagle-import:0805")
      (libsource (lib "eagle-import") (part "RESISTOR0805"))
    )
    (comp (ref "R33")
      (value "RESISTOR0805")
      (footprint "eagle-import:0805")
      (libsource (lib "eagle-import") (part "RESISTOR0805"))
    )
    (comp (ref "R34")
      (value "RESISTOR0805")
      (footprint "eagle-import:0805")
      (libsource (lib "eagle-import") (part "RESISTOR0805"))
    )
    (comp (ref "R35")
      (value "RESISTOR0805")
      (footprint "eagle-import:0805")
      (libsource (lib "eagle-import") (part "RESISTOR0805"))
    )
    (comp (ref "R36")
      (value "RESISTOR0805")
      (footprint "eagle-import:0805")
      (libsource (lib "eagle-import") (part "RESISTOR0805"))
    )
    (comp (ref "R37")
      (value "RESISTOR0805")
      (footprint "eagle-import:0805")
      (libsource (lib "eagle-import") (part "RESISTOR0805"))
    )
    (comp (ref "R38")
      (value "RESISTOR0805")
      (footprint "eagle-import:0805")
      (libsource (lib "eagle-import") (part "RESISTOR0805"))
    )
    (comp (ref "R39")
      (value "RESISTOR0805")
      (footprint "eagle-import:0805")
      (libsource (lib "eagle-import") (part "RESISTOR0805"))
    )
    (comp (ref "R40")
      (value "RESISTOR0805")
      (footprint "eagle-import:0805")
      (libsource (lib "eagle-import") (part "RESISTOR0805"))
    )
    (comp (ref "R41")
      (value "RESISTOR0805")
      (footprint "eagle-import:0805")
      (libsource (lib "eagle-import") (part "RESISTOR0805"))
    )
    (comp (ref "R42")
      (value "RESISTOR0805")
      (footprint "eagle-import:0805")
      (libsource (lib "eagle-import") (part "RESISTOR0805"))
    )
    (comp (ref "R43")
      (value "RESISTOR0805")
      (footprint "eagle-import:0805")
      (libsource (lib "eagle-import") (part "RESISTOR0805"))
    )
    (comp (ref "R44")
      (value "RESISTOR0805")
      (footprint "eagle-import:0805")
      (libsource (lib "eagle-import") (part "RESISTOR0805"))
    )
    (comp (ref "R45")
      (value "RESISTOR0805")
      (footprint "eagle-import:0805")
      (libsource (lib "eagle-import") (part "RESISTOR0805"))
    )
    (comp (ref "R46")
      (value "RESISTOR0805")
      (footprint "eagle-import:0805")
      (libsource (lib "eagle-import") (part "RESISTOR0805"))
    )
    (comp (ref "R47")
      (value "RESISTOR0805")
      (footprint "eagle-import:0805")
      (libsource (lib "eagle-import") (part "RESISTOR0805"))
    )
    (comp (ref "R48")
      (value "RESISTOR0805")
      (footprint "eagle-import:0805")
      (libsource (lib "eagle-import") (part "RESISTOR0805"))
    )
    (comp (ref "R49")
      (value "RESISTOR0805")
      (footprint "eagle-import:0805")
      (libsource (lib "eagle-import") (part "RESISTOR0805"))
    )
    (comp (ref "R50")
      (value "RESISTOR0805")
      (footprint "eagle-import:0805")
      (libsource (lib "eagle-import") (part "RESISTOR0805"))
    )
    (comp (ref "R51")
      (value "RESISTOR0805")
      (footprint "eagle-import:0805")
      (libsource (lib "eagle-import") (part "RESISTOR0805"))
    )
    (comp (ref "R52")
      (value "RESISTOR0805")
      (footprint "eagle-import:0805")
      (libsource (lib "eagle-import") (part "RESISTOR0805"))
    )
    (comp (ref "R53")
      (value "RESISTOR0805")
      (footprint "eagle-import:0805")
      (libsource (lib "eagle-import") (part "RESISTOR0805"))
    )
    (comp (ref "R54")
      (value "RESISTOR0805")
      (footprint "eagle-import:0805")
      (libsource (lib "eagle-import") (part "RESISTOR0805"))
    )
    (comp (ref "R55")
      (value "RESISTOR0805")
      (footprint "eagle-import:0805")
      (libsource (lib "eagle-import") (part "RESISTOR0805"))
    )
    (comp (ref "R56")
      (value "RESISTOR0805")
      (footprint "eagle-import:0805")
      (libsource (lib "eagle-import") (part "RESISTOR0805"))
    )
    (comp (ref "R57")
      (value "RESISTOR0805")
      (footprint "eagle-import:0805")
      (libsource (lib "eagle-import") (part "RESISTOR0805"))
    )
    (comp (ref "R58")
      (value "RESISTOR0805")
      (footprint "eagle-import:0805")
      (libsource (lib "eagle-import") (part "RESISTOR0805"))
    )
    (comp (ref "R59")
      (value "RESISTOR0805")
      (footprint "eagle-import:0805")
      (libsource (lib "eagle-import") (part "RESISTOR0805"))
    )
    (comp (ref "R60")
      (value "RESISTOR0805")
      (footprint "eagle-import:0805")
      (libsource (lib "eagle-import") (part "RESISTOR0805"))
    )
    (comp (ref "R61")
      (value "RESISTOR0805")
      (footprint "eagle-import:0805")
      (libsource (lib "eagle-import") (part "RESISTOR0805"))
    )
    (comp (ref "R62")
      (value "RESISTOR0805")
      (footprint "eagle-import:0805")
      (libsource (lib "eagle-import") (part "RESISTOR0805"))
    )
    (comp (ref "R63")
      (value "RESISTOR0805")
      (footprint "eagle-import:0805")
      (libsource (lib "eagle-import") (part "RESISTOR0805"))
    )
    (comp (ref "R64")
      (value "RESISTOR0805")
      (footprint "eagle-import:0805")
      (libsource (lib "eagle-import") (part "RESISTOR0805"))
    )
    (comp (ref "R65")
      (value "RESISTOR0805")
      (footprint "eagle-import:0805")
      (libsource (lib "eagle-import") (part "RESISTOR0805"))
    )
    (comp (ref "R66")
      (value "RESISTOR0805")
      (footprint "eagle-import:0805")
      (libsource (lib "eagle-import") (part "RESISTOR0805"))
    )
    (comp (ref "R67")
      (value "RESISTOR0805")
      (footprint "eagle-import:0805")
      (libsource (lib "eagle-import") (part "RESISTOR0805"))
    )
    (comp (ref "R68")
      (value "RESISTOR0805")
      (footprint "eagle-import:0805")
      (libsource (lib "eagle-import") (part "RESISTOR0805"))
    )
    (comp (ref "R69")
      (value "RESISTOR0805")
      (footprint "eagle-import:0805")
      (libsource (lib "eagle-import") (part "RESISTOR0805"))
    )
    (comp (ref "R70")
      (value "RESISTOR0805")
      (footprint "eagle-import:0805")
      (libsource (lib "eagle-import") (part "RESISTOR0805"))
    )
    (comp (ref "SJ1")
      (value "SJ2W")
      (footprint "eagle-import:SJ_2")
      (libsource (lib "eagle-import") (part "SJ2W"))
    )
    (comp (ref "SJ2")
      (value "SJ2W")
      (footprint "eagle-import:SJ_2")
      (libsource (lib "eagle-import") (part "SJ2W"))
    )
  )
  (nets
    (net (code "1") (name "/AUX0A'") (class "Default")
      (node (ref "Q104") (pin "1") (pinfunction "G_1") (pintype "bidirectional"))
      (node (ref "Q114") (pin "3") (pinfunction "D_3") (pintype "bidirectional"))
      (node (ref "Q115") (pin "3") (pinfunction "D_3") (pintype "bidirectional"))
      (node (ref "Q116") (pin "3") (pinfunction "D_3") (pintype "bidirectional"))
      (node (ref "R48") (pin "2") (pinfunction "2_2") (pintype "passive"))
    )
    (net (code "2") (name "/AUX1A'-") (class "Default")
      (node (ref "Q71") (pin "1") (pinfunction "G_1") (pintype "bidirectional"))
      (node (ref "Q81") (pin "3") (pinfunction "D_3") (pintype "bidirectional"))
      (node (ref "Q82") (pin "3") (pinfunction "D_3") (pintype "bidirectional"))
      (node (ref "Q83") (pin "3") (pinfunction "D_3") (pintype "bidirectional"))
      (node (ref "R34") (pin "2") (pinfunction "2_2") (pintype "passive"))
    )
    (net (code "3") (name "/AUX2A'") (class "Default")
      (node (ref "Q13") (pin "1") (pinfunction "G_1") (pintype "bidirectional"))
      (node (ref "Q31") (pin "3") (pinfunction "D_3") (pintype "bidirectional"))
      (node (ref "Q32") (pin "3") (pinfunction "D_3") (pintype "bidirectional"))
      (node (ref "Q34") (pin "3") (pinfunction "D_3") (pintype "bidirectional"))
      (node (ref "R12") (pin "2") (pinfunction "2_2") (pintype "passive"))
    )
    (net (code "4") (name "/AUX3A'") (class "Default")
      (node (ref "Q137") (pin "1") (pinfunction "G_1") (pintype "bidirectional"))
      (node (ref "Q147") (pin "3") (pinfunction "D_3") (pintype "bidirectional"))
      (node (ref "Q148") (pin "3") (pinfunction "D_3") (pintype "bidirectional"))
      (node (ref "Q149") (pin "3") (pinfunction "D_3") (pintype "bidirectional"))
      (node (ref "R62") (pin "2") (pinfunction "2_2") (pintype "passive"))
    )
    (net (code "5") (name "/LOAD0A'") (class "Default")
      (node (ref "Q103") (pin "1") (pinfunction "G_1") (pintype "bidirectional"))
      (node (ref "Q111") (pin "3") (pinfunction "D_3") (pintype "bidirectional"))
      (node (ref "Q112") (pin "3") (pinfunction "D_3") (pintype "bidirectional"))
      (node (ref "Q113") (pin "3") (pinfunction "D_3") (pintype "bidirectional"))
      (node (ref "R47") (pin "2") (pinfunction "2_2") (pintype "passive"))
    )
    (net (code "6") (name "/LOAD1A'-") (class "Default")
      (node (ref "Q70") (pin "1") (pinfunction "G_1") (pintype "bidirectional"))
      (node (ref "Q78") (pin "3") (pinfunction "D_3") (pintype "bidirectional"))
      (node (ref "Q79") (pin "3") (pinfunction "D_3") (pintype "bidirectional"))
      (node (ref "Q80") (pin "3") (pinfunction "D_3") (pintype "bidirectional"))
      (node (ref "R33") (pin "2") (pinfunction "2_2") (pintype "passive"))
    )
    (net (code "7") (name "/LOAD2A'") (class "Default")
      (node (ref "Q12") (pin "1") (pinfunction "G_1") (pintype "bidirectional"))
      (node (ref "Q28") (pin "3") (pinfunction "D_3") (pintype "bidirectional"))
      (node (ref "Q29") (pin "3") (pinfunction "D_3") (pintype "bidirectional"))
      (node (ref "Q30") (pin "3") (pinfunction "D_3") (pintype "bidirectional"))
      (node (ref "R11") (pin "2") (pinfunction "2_2") (pintype "passive"))
    )
    (net (code "8") (name "/LOAD3A'") (class "Default")
      (node (ref "Q136") (pin "1") (pinfunction "G_1") (pintype "bidirectional"))
      (node (ref "Q144") (pin "3") (pinfunction "D_3") (pintype "bidirectional"))
      (node (ref "Q145") (pin "3") (pinfunction "D_3") (pintype "bidirectional"))
      (node (ref "Q146") (pin "3") (pinfunction "D_3") (pintype "bidirectional"))
      (node (ref "R61") (pin "2") (pinfunction "2_2") (pintype "passive"))
    )
    (net (code "9") (name "/NEXT0A'") (class "Default")
      (node (ref "Q102") (pin "1") (pinfunction "G_1") (pintype "bidirectional"))
      (node (ref "Q108") (pin "3") (pinfunction "D_3") (pintype "bidirectional"))
      (node (ref "Q109") (pin "3") (pinfunction "D_3") (pintype "bidirectional"))
      (node (ref "Q110") (pin "3") (pinfunction "D_3") (pintype "bidirectional"))
      (node (ref "R46") (pin "2") (pinfunction "2_2") (pintype "passive"))
    )
    (net (code "10") (name "/NEXT1A'") (class "Default")
      (node (ref "Q69") (pin "1") (pinfunction "G_1") (pintype "bidirectional"))
      (node (ref "Q75") (pin "3") (pinfunction "D_3") (pintype "bidirectional"))
      (node (ref "Q76") (pin "3") (pinfunction "D_3") (pintype "bidirectional"))
      (node (ref "Q77") (pin "3") (pinfunction "D_3") (pintype "bidirectional"))
      (node (ref "R32") (pin "2") (pinfunction "2_2") (pintype "passive"))
    )
    (net (code "11") (name "/NEXT2A'") (class "Default")
      (node (ref "Q11") (pin "1") (pinfunction "G_1") (pintype "bidirectional"))
      (node (ref "Q25") (pin "3") (pinfunction "D_3") (pintype "bidirectional"))
      (node (ref "Q26") (pin "3") (pinfunction "D_3") (pintype "bidirectional"))
      (node (ref "Q27") (pin "3") (pinfunction "D_3") (pintype "bidirectional"))
      (node (ref "R8") (pin "2") (pinfunction "2_2") (pintype "passive"))
    )
    (net (code "12") (name "/NEXT3A'") (class "Default")
      (node (ref "Q135") (pin "1") (pinfunction "G_1") (pintype "bidirectional"))
      (node (ref "Q141") (pin "3") (pinfunction "D_3") (pintype "bidirectional"))
      (node (ref "Q142") (pin "3") (pinfunction "D_3") (pintype "bidirectional"))
      (node (ref "Q143") (pin "3") (pinfunction "D_3") (pintype "bidirectional"))
      (node (ref "R60") (pin "2") (pinfunction "2_2") (pintype "passive"))
    )
    (net (code "13") (name "/PREV0A'") (class "Default")
      (node (ref "Q101") (pin "1") (pinfunction "G_1") (pintype "bidirectional"))
      (node (ref "Q105") (pin "3") (pinfunction "D_3") (pintype "bidirectional"))
      (node (ref "Q106") (pin "3") (pinfunction "D_3") (pintype "bidirectional"))
      (node (ref "Q107") (pin "3") (pinfunction "D_3") (pintype "bidirectional"))
      (node (ref "R45") (pin "2") (pinfunction "2_2") (pintype "passive"))
    )
    (net (code "14") (name "/PREV1A'") (class "Default")
      (node (ref "Q68") (pin "1") (pinfunction "G_1") (pintype "bidirectional"))
      (node (ref "Q72") (pin "3") (pinfunction "D_3") (pintype "bidirectional"))
      (node (ref "Q73") (pin "3") (pinfunction "D_3") (pintype "bidirectional"))
      (node (ref "Q74") (pin "3") (pinfunction "D_3") (pintype "bidirectional"))
      (node (ref "R31") (pin "2") (pinfunction "2_2") (pintype "passive"))
    )
    (net (code "15") (name "/PREV2A'") (class "Default")
      (node (ref "Q10") (pin "1") (pinfunction "G_1") (pintype "bidirectional"))
      (node (ref "Q14") (pin "3") (pinfunction "D_3") (pintype "bidirectional"))
      (node (ref "Q15") (pin "3") (pinfunction "D_3") (pintype "bidirectional"))
      (node (ref "Q16") (pin "3") (pinfunction "D_3") (pintype "bidirectional"))
      (node (ref "R7") (pin "2") (pinfunction "2_2") (pintype "passive"))
    )
    (net (code "16") (name "/PREV3A'") (class "Default")
      (node (ref "Q134") (pin "1") (pinfunction "G_1") (pintype "bidirectional"))
      (node (ref "Q138") (pin "3") (pinfunction "D_3") (pintype "bidirectional"))
      (node (ref "Q139") (pin "3") (pinfunction "D_3") (pintype "bidirectional"))
      (node (ref "Q140") (pin "3") (pinfunction "D_3") (pintype "bidirectional"))
      (node (ref "R59") (pin "2") (pinfunction "2_2") (pintype "passive"))
    )
    (net (code "17") (name "/R0A-") (class "Default")
      (node (ref "Q100") (pin "3") (pinfunction "D_3") (pintype "bidirectional"))
      (node (ref "Q121") (pin "1") (pinfunction "G_1") (pintype "bidirectional"))
      (node (ref "R43") (pin "2") (pinfunction "2_2") (pintype "passive"))
    )
    (net (code "18") (name "/R1A") (class "Default")
      (node (ref "Q67") (pin "3") (pinfunction "D_3") (pintype "bidirectional"))
      (node (ref "Q88") (pin "1") (pinfunction "G_1") (pintype "bidirectional"))
      (node (ref "R25") (pin "2") (pinfunction "2_2") (pintype "passive"))
    )
    (net (code "19") (name "/R2A") (class "Default")
      (node (ref "Q39") (pin "1") (pinfunction "G_1") (pintype "bidirectional"))
      (node (ref "Q9") (pin "3") (pinfunction "D_3") (pintype "bidirectional"))
      (node (ref "R5") (pin "2") (pinfunction "2_2") (pintype "passive"))
    )
    (net (code "20") (name "/R3A") (class "Default")
      (node (ref "Q133") (pin "3") (pinfunction "D_3") (pintype "bidirectional"))
      (node (ref "Q154") (pin "1") (pinfunction "G_1") (pintype "bidirectional"))
      (node (ref "R57") (pin "2") (pinfunction "2_2") (pintype "passive"))
    )
    (net (code "21") (name "/S0A-") (class "Default")
      (node (ref "Q100") (pin "1") (pinfunction "G_1") (pintype "bidirectional"))
      (node (ref "Q101") (pin "3") (pinfunction "D_3") (pintype "bidirectional"))
      (node (ref "Q102") (pin "3") (pinfunction "D_3") (pintype "bidirectional"))
      (node (ref "Q103") (pin "3") (pinfunction "D_3") (pintype "bidirectional"))
      (node (ref "Q104") (pin "3") (pinfunction "D_3") (pintype "bidirectional"))
      (node (ref "Q118") (pin "1") (pinfunction "G_1") (pintype "bidirectional"))
      (node (ref "R44") (pin "2") (pinfunction "2_2") (pintype "passive"))
    )
    (net (code "22") (name "/S1A") (class "Default")
      (node (ref "Q67") (pin "1") (pinfunction "G_1") (pintype "bidirectional"))
      (node (ref "Q68") (pin "3") (pinfunction "D_3") (pintype "bidirectional"))
      (node (ref "Q69") (pin "3") (pinfunction "D_3") (pintype "bidirectional"))
      (node (ref "Q70") (pin "3") (pinfunction "D_3") (pintype "bidirectional"))
      (node (ref "Q71") (pin "3") (pinfunction "D_3") (pintype "bidirectional"))
      (node (ref "Q85") (pin "1") (pinfunction "G_1") (pintype "bidirectional"))
      (node (ref "R26") (pin "2") (pinfunction "2_2") (pintype "passive"))
    )
    (net (code "23") (name "/S2A") (class "Default")
      (node (ref "Q10") (pin "3") (pinfunction "D_3") (pintype "bidirectional"))
      (node (ref "Q11") (pin "3") (pinfunction "D_3") (pintype "bidirectional"))
      (node (ref "Q12") (pin "3") (pinfunction "D_3") (pintype "bidirectional"))
      (node (ref "Q13") (pin "3") (pinfunction "D_3") (pintype "bidirectional"))
      (node (ref "Q36") (pin "1") (pinfunction "G_1") (pintype "bidirectional"))
      (node (ref "Q9") (pin "1") (pinfunction "G_1") (pintype "bidirectional"))
      (node (ref "R6") (pin "2") (pinfunction "2_2") (pintype "passive"))
    )
    (net (code "24") (name "/S3A") (class "Default")
      (node (ref "Q133") (pin "1") (pinfunction "G_1") (pintype "bidirectional"))
      (node (ref "Q134") (pin "3") (pinfunction "D_3") (pintype "bidirectional"))
      (node (ref "Q135") (pin "3") (pinfunction "D_3") (pintype "bidirectional"))
      (node (ref "Q136") (pin "3") (pinfunction "D_3") (pintype "bidirectional"))
      (node (ref "Q137") (pin "3") (pinfunction "D_3") (pintype "bidirectional"))
      (node (ref "Q151") (pin "1") (pinfunction "G_1") (pintype "bidirectional"))
      (node (ref "R58") (pin "2") (pinfunction "2_2") (pintype "passive"))
    )
    (net (code "25") (name "AUX0") (class "Default")
      (node (ref "JP2") (pin "20") (pinfunction "20_20") (pintype "passive"))
      (node (ref "Q116") (pin "1") (pinfunction "G_1") (pintype "bidirectional"))
    )
    (net (code "26") (name "AUX1") (class "Default")
      (node (ref "JP2") (pin "21") (pinfunction "21_21") (pintype "passive"))
      (node (ref "Q83") (pin "1") (pinfunction "G_1") (pintype "bidirectional"))
    )
    (net (code "27") (name "AUX2") (class "Default")
      (node (ref "JP2") (pin "22") (pinfunction "22_22") (pintype "passive"))
      (node (ref "Q34") (pin "1") (pinfunction "G_1") (pintype "bidirectional"))
    )
    (net (code "28") (name "AUX3") (class "Default")
      (node (ref "JP2") (pin "23") (pinfunction "23_23") (pintype "passive"))
      (node (ref "Q149") (pin "1") (pinfunction "G_1") (pintype "bidirectional"))
    )
    (net (code "29") (name "CLK") (class "Default")
      (node (ref "Q125") (pin "1") (pinfunction "G_1") (pintype "bidirectional"))
      (node (ref "Q128") (pin "1") (pinfunction "G_1") (pintype "bidirectional"))
      (node (ref "Q158") (pin "1") (pinfunction "G_1") (pintype "bidirectional"))
      (node (ref "Q161") (pin "1") (pinfunction "G_1") (pintype "bidirectional"))
      (node (ref "Q51") (pin "1") (pinfunction "G_1") (pintype "bidirectional"))
      (node (ref "Q54") (pin "1") (pinfunction "G_1") (pintype "bidirectional"))
      (node (ref "Q92") (pin "1") (pinfunction "G_1") (pintype "bidirectional"))
      (node (ref "Q95") (pin "1") (pinfunction "G_1") (pintype "bidirectional"))
      (node (ref "SJ1") (pin "1") (pinfunction "1_1") (pintype "passive"))
      (node (ref "SJ2") (pin "1") (pinfunction "1_1") (pintype "passive"))
    )
    (net (code "30") (name "CLK_IN") (class "Default")
      (node (ref "JP2") (pin "1") (pinfunction "1_1") (pintype "passive"))
      (node (ref "Q21") (pin "1") (pinfunction "G_1") (pintype "bidirectional"))
      (node (ref "SJ2") (pin "2") (pinfunction "2_2") (pintype "passive"))
    )
    (net (code "31") (name "CLR") (class "Default")
      (node (ref "JP2") (pin "4") (pinfunction "4_4") (pintype "passive"))
      (node (ref "Q17") (pin "1") (pinfunction "G_1") (pintype "bidirectional"))
      (node (ref "Q18") (pin "1") (pinfunction "G_1") (pintype "bidirectional"))
      (node (ref "Q19") (pin "1") (pinfunction "G_1") (pintype "bidirectional"))
      (node (ref "Q20") (pin "1") (pinfunction "G_1") (pintype "bidirectional"))
      (node (ref "Q5") (pin "1") (pinfunction "G_1") (pintype "bidirectional"))
      (node (ref "Q6") (pin "1") (pinfunction "G_1") (pintype "bidirectional"))
      (node (ref "Q7") (pin "1") (pinfunction "G_1") (pintype "bidirectional"))
      (node (ref "Q8") (pin "1") (pinfunction "G_1") (pintype "bidirectional"))
    )
    (net (code "32") (name "GND") (class "Default")
      (node (ref "C1") (pin "2") (pinfunction "2_2") (pintype "passive"))
      (node (ref "C2") (pin "2") (pinfunction "2_2") (pintype "passive"))
      (node (ref "C3") (pin "2") (pinfunction "2_2") (pintype "passive"))
      (node (ref "C4") (pin "2") (pinfunction "2_2") (pintype "passive"))
      (node (ref "C5") (pin "2") (pinfunction "2_2") (pintype "passive"))
      (node (ref "JP2") (pin "30") (pinfunction "30_30") (pintype "passive"))
      (node (ref "Q1") (pin "2") (pinfunction "S_2") (pintype "bidirectional"))
      (node (ref "Q10") (pin "2") (pinfunction "S_2") (pintype "bidirectional"))
      (node (ref "Q100") (pin "2") (pinfunction "S_2") (pintype "bidirectional"))
      (node (ref "Q101") (pin "2") (pinfunction "S_2") (pintype "bidirectional"))
      (node (ref "Q102") (pin "2") (pinfunction "S_2") (pintype "bidirectional"))
      (node (ref "Q103") (pin "2") (pinfunction "S_2") (pintype "bidirectional"))
      (node (ref "Q104") (pin "2") (pinfunction "S_2") (pintype "bidirectional"))
      (node (ref "Q105") (pin "2") (pinfunction "S_2") (pintype "bidirectional"))
      (node (ref "Q106") (pin "2") (pinfunction "S_2") (pintype "bidirectional"))
      (node (ref "Q107") (pin "2") (pinfunction "S_2") (pintype "bidirectional"))
      (node (ref "Q108") (pin "2") (pinfunction "S_2") (pintype "bidirectional"))
      (node (ref "Q109") (pin "2") (pinfunction "S_2") (pintype "bidirectional"))
      (node (ref "Q11") (pin "2") (pinfunction "S_2") (pintype "bidirectional"))
      (node (ref "Q110") (pin "2") (pinfunction "S_2") (pintype "bidirectional"))
      (node (ref "Q111") (pin "2") (pinfunction "S_2") (pintype "bidirectional"))
      (node (ref "Q112") (pin "2") (pinfunction "S_2") (pintype "bidirectional"))
      (node (ref "Q113") (pin "2") (pinfunction "S_2") (pintype "bidirectional"))
      (node (ref "Q114") (pin "2") (pinfunction "S_2") (pintype "bidirectional"))
      (node (ref "Q115") (pin "2") (pinfunction "S_2") (pintype "bidirectional"))
      (node (ref "Q116") (pin "2") (pinfunction "S_2") (pintype "bidirectional"))
      (node (ref "Q117") (pin "2") (pinfunction "S_2") (pintype "bidirectional"))
      (node (ref "Q118") (pin "2") (pinfunction "S_2") (pintype "bidirectional"))
      (node (ref "Q119") (pin "2") (pinfunction "S_2") (pintype "bidirectional"))
      (node (ref "Q12") (pin "2") (pinfunction "S_2") (pintype "bidirectional"))
      (node (ref "Q120") (pin "2") (pinfunction "S_2") (pintype "bidirectional"))
      (node (ref "Q121") (pin "2") (pinfunction "S_2") (pintype "bidirectional"))
      (node (ref "Q122") (pin "2") (pinfunction "S_2") (pintype "bidirectional"))
      (node (ref "Q123") (pin "2") (pinfunction "S_2") (pintype "bidirectional"))
      (node (ref "Q124") (pin "2") (pinfunction "S_2") (pintype "bidirectional"))
      (node (ref "Q125") (pin "2") (pinfunction "S_2") (pintype "bidirectional"))
      (node (ref "Q126") (pin "2") (pinfunction "S_2") (pintype "bidirectional"))
      (node (ref "Q127") (pin "2") (pinfunction "S_2") (pintype "bidirectional"))
      (node (ref "Q128") (pin "2") (pinfunction "S_2") (pintype "bidirectional"))
      (node (ref "Q129") (pin "2") (pinfunction "S_2") (pintype "bidirectional"))
      (node (ref "Q13") (pin "2") (pinfunction "S_2") (pintype "bidirectional"))
      (node (ref "Q130") (pin "2") (pinfunction "S_2") (pintype "bidirectional"))
      (node (ref "Q131") (pin "2") (pinfunction "S_2") (pintype "bidirectional"))
      (node (ref "Q132") (pin "2") (pinfunction "S_2") (pintype "bidirectional"))
      (node (ref "Q133") (pin "2") (pinfunction "S_2") (pintype "bidirectional"))
      (node (ref "Q134") (pin "2") (pinfunction "S_2") (pintype "bidirectional"))
      (node (ref "Q135") (pin "2") (pinfunction "S_2") (pintype "bidirectional"))
      (node (ref "Q136") (pin "2") (pinfunction "S_2") (pintype "bidirectional"))
      (node (ref "Q137") (pin "2") (pinfunction "S_2") (pintype "bidirectional"))
      (node (ref "Q138") (pin "2") (pinfunction "S_2") (pintype "bidirectional"))
      (node (ref "Q139") (pin "2") (pinfunction "S_2") (pintype "bidirectional"))
      (node (ref "Q14") (pin "2") (pinfunction "S_2") (pintype "bidirectional"))
      (node (ref "Q140") (pin "2") (pinfunction "S_2") (pintype "bidirectional"))
      (node (ref "Q141") (pin "2") (pinfunction "S_2") (pintype "bidirectional"))
      (node (ref "Q142") (pin "2") (pinfunction "S_2") (pintype "bidirectional"))
      (node (ref "Q143") (pin "2") (pinfunction "S_2") (pintype "bidirectional"))
      (node (ref "Q144") (pin "2") (pinfunction "S_2") (pintype "bidirectional"))
      (node (ref "Q145") (pin "2") (pinfunction "S_2") (pintype "bidirectional"))
      (node (ref "Q146") (pin "2") (pinfunction "S_2") (pintype "bidirectional"))
      (node (ref "Q147") (pin "2") (pinfunction "S_2") (pintype "bidirectional"))
      (node (ref "Q148") (pin "2") (pinfunction "S_2") (pintype "bidirectional"))
      (node (ref "Q149") (pin "2") (pinfunction "S_2") (pintype "bidirectional"))
      (node (ref "Q15") (pin "2") (pinfunction "S_2") (pintype "bidirectional"))
      (node (ref "Q150") (pin "2") (pinfunction "S_2") (pintype "bidirectional"))
      (node (ref "Q151") (pin "2") (pinfunction "S_2") (pintype "bidirectional"))
      (node (ref "Q152") (pin "2") (pinfunction "S_2") (pintype "bidirectional"))
      (node (ref "Q153") (pin "2") (pinfunction "S_2") (pintype "bidirectional"))
      (node (ref "Q154") (pin "2") (pinfunction "S_2") (pintype "bidirectional"))
      (node (ref "Q155") (pin "2") (pinfunction "S_2") (pintype "bidirectional"))
      (node (ref "Q156") (pin "2") (pinfunction "S_2") (pintype "bidirectional"))
      (node (ref "Q157") (pin "2") (pinfunction "S_2") (pintype "bidirectional"))
      (node (ref "Q158") (pin "2") (pinfunction "S_2") (pintype "bidirectional"))
      (node (ref "Q159") (pin "2") (pinfunction "S_2") (pintype "bidirectional"))
      (node (ref "Q16") (pin "2") (pinfunction "S_2") (pintype "bidirectional"))
      (node (ref "Q160") (pin "2") (pinfunction "S_2") (pintype "bidirectional"))
      (node (ref "Q161") (pin "2") (pinfunction "S_2") (pintype "bidirectional"))
      (node (ref "Q162") (pin "2") (pinfunction "S_2") (pintype "bidirectional"))
      (node (ref "Q163") (pin "2") (pinfunction "S_2") (pintype "bidirectional"))
      (node (ref "Q164") (pin "2") (pinfunction "S_2") (pintype "bidirectional"))
      (node (ref "Q165") (pin "2") (pinfunction "S_2") (pintype "bidirectional"))
      (node (ref "Q17") (pin "2") (pinfunction "S_2") (pintype "bidirectional"))
      (node (ref "Q18") (pin "2") (pinfunction "S_2") (pintype "bidirectional"))
      (node (ref "Q19") (pin "2") (pinfunction "S_2") (pintype "bidirectional"))
      (node (ref "Q2") (pin "2") (pinfunction "S_2") (pintype "bidirectional"))
      (node (ref "Q20") (pin "2") (pinfunction "S_2") (pintype "bidirectional"))
      (node (ref "Q21") (pin "2") (pinfunction "S_2") (pintype "bidirectional"))
      (node (ref "Q22") (pin "2") (pinfunction "S_2") (pintype "bidirectional"))
      (node (ref "Q23") (pin "2") (pinfunction "S_2") (pintype "bidirectional"))
      (node (ref "Q25") (pin "2") (pinfunction "S_2") (pintype "bidirectional"))
      (node (ref "Q26") (pin "2") (pinfunction "S_2") (pintype "bidirectional"))
      (node (ref "Q27") (pin "2") (pinfunction "S_2") (pintype "bidirectional"))
      (node (ref "Q28") (pin "2") (pinfunction "S_2") (pintype "bidirectional"))
      (node (ref "Q29") (pin "2") (pinfunction "S_2") (pintype "bidirectional"))
      (node (ref "Q3") (pin "2") (pinfunction "S_2") (pintype "bidirectional"))
      (node (ref "Q30") (pin "2") (pinfunction "S_2") (pintype "bidirectional"))
      (node (ref "Q31") (pin "2") (pinfunction "S_2") (pintype "bidirectional"))
      (node (ref "Q32") (pin "2") (pinfunction "S_2") (pintype "bidirectional"))
      (node (ref "Q34") (pin "2") (pinfunction "S_2") (pintype "bidirectional"))
      (node (ref "Q35") (pin "2") (pinfunction "S_2") (pintype "bidirectional"))
      (node (ref "Q36") (pin "2") (pinfunction "S_2") (pintype "bidirectional"))
      (node (ref "Q37") (pin "2") (pinfunction "S_2") (pintype "bidirectional"))
      (node (ref "Q38") (pin "2") (pinfunction "S_2") (pintype "bidirectional"))
      (node (ref "Q39") (pin "2") (pinfunction "S_2") (pintype "bidirectional"))
      (node (ref "Q4") (pin "2") (pinfunction "S_2") (pintype "bidirectional"))
      (node (ref "Q40") (pin "2") (pinfunction "S_2") (pintype "bidirectional"))
      (node (ref "Q41") (pin "2") (pinfunction "S_2") (pintype "bidirectional"))
      (node (ref "Q5") (pin "2") (pinfunction "S_2") (pintype "bidirectional"))
      (node (ref "Q50") (pin "2") (pinfunction "S_2") (pintype "bidirectional"))
      (node (ref "Q51") (pin "2") (pinfunction "S_2") (pintype "bidirectional"))
      (node (ref "Q52") (pin "2") (pinfunction "S_2") (pintype "bidirectional"))
      (node (ref "Q53") (pin "2") (pinfunction "S_2") (pintype "bidirectional"))
      (node (ref "Q54") (pin "2") (pinfunction "S_2") (pintype "bidirectional"))
      (node (ref "Q55") (pin "2") (pinfunction "S_2") (pintype "bidirectional"))
      (node (ref "Q56") (pin "2") (pinfunction "S_2") (pintype "bidirectional"))
      (node (ref "Q57") (pin "2") (pinfunction "S_2") (pintype "bidirectional"))
      (node (ref "Q6") (pin "2") (pinfunction "S_2") (pintype "bidirectional"))
      (node (ref "Q66") (pin "2") (pinfunction "S_2") (pintype "bidirectional"))
      (node (ref "Q67") (pin "2") (pinfunction "S_2") (pintype "bidirectional"))
      (node (ref "Q68") (pin "2") (pinfunction "S_2") (pintype "bidirectional"))
      (node (ref "Q69") (pin "2") (pinfunction "S_2") (pintype "bidirectional"))
      (node (ref "Q7") (pin "2") (pinfunction "S_2") (pintype "bidirectional"))
      (node (ref "Q70") (pin "2") (pinfunction "S_2") (pintype "bidirectional"))
      (node (ref "Q71") (pin "2") (pinfunction "S_2") (pintype "bidirectional"))
      (node (ref "Q72") (pin "2") (pinfunction "S_2") (pintype "bidirectional"))
      (node (ref "Q73") (pin "2") (pinfunction "S_2") (pintype "bidirectional"))
      (node (ref "Q74") (pin "2") (pinfunction "S_2") (pintype "bidirectional"))
      (node (ref "Q75") (pin "2") (pinfunction "S_2") (pintype "bidirectional"))
      (node (ref "Q76") (pin "2") (pinfunction "S_2") (pintype "bidirectional"))
      (node (ref "Q77") (pin "2") (pinfunction "S_2") (pintype "bidirectional"))
      (node (ref "Q78") (pin "2") (pinfunction "S_2") (pintype "bidirectional"))
      (node (ref "Q79") (pin "2") (pinfunction "S_2") (pintype "bidirectional"))
      (node (ref "Q8") (pin "2") (pinfunction "S_2") (pintype "bidirectional"))
      (node (ref "Q80") (pin "2") (pinfunction "S_2") (pintype "bidirectional"))
      (node (ref "Q81") (pin "2") (pinfunction "S_2") (pintype "bidirectional"))
      (node (ref "Q82") (pin "2") (pinfunction "S_2") (pintype "bidirectional"))
      (node (ref "Q83") (pin "2") (pinfunction "S_2") (pintype "bidirectional"))
      (node (ref "Q84") (pin "2") (pinfunction "S_2") (pintype "bidirectional"))
      (node (ref "Q85") (pin "2") (pinfunction "S_2") (pintype "bidirectional"))
      (node (ref "Q86") (pin "2") (pinfunction "S_2") (pintype "bidirectional"))
      (node (ref "Q87") (pin "2") (pinfunction "S_2") (pintype "bidirectional"))
      (node (ref "Q88") (pin "2") (pinfunction "S_2") (pintype "bidirectional"))
      (node (ref "Q89") (pin "2") (pinfunction "S_2") (pintype "bidirectional"))
      (node (ref "Q9") (pin "2") (pinfunction "S_2") (pintype "bidirectional"))
      (node (ref "Q90") (pin "2") (pinfunction "S_2") (pintype "bidirectional"))
      (node (ref "Q91") (pin "2") (pinfunction "S_2") (pintype "bidirectional"))
      (node (ref "Q92") (pin "2") (pinfunction "S_2") (pintype "bidirectional"))
      (node (ref "Q93") (pin "2") (pinfunction "S_2") (pintype "bidirectional"))
      (node (ref "Q94") (pin "2") (pinfunction "S_2") (pintype "bidirectional"))
      (node (ref "Q95") (pin "2") (pinfunction "S_2") (pintype "bidirectional"))
      (node (ref "Q96") (pin "2") (pinfunction "S_2") (pintype "bidirectional"))
      (node (ref "Q97") (pin "2") (pinfunction "S_2") (pintype "bidirectional"))
      (node (ref "Q98") (pin "2") (pinfunction "S_2") (pintype "bidirectional"))
      (node (ref "Q99") (pin "2") (pinfunction "S_2") (pintype "bidirectional"))
    )
    (net (code "33") (name "LOAD0") (class "Default")
      (node (ref "JP2") (pin "16") (pinfunction "16_16") (pintype "passive"))
      (node (ref "Q113") (pin "1") (pinfunction "G_1") (pintype "bidirectional"))
    )
    (net (code "34") (name "LOAD1") (class "Default")
      (node (ref "JP2") (pin "17") (pinfunction "17_17") (pintype "passive"))
      (node (ref "Q80") (pin "1") (pinfunction "G_1") (pintype "bidirectional"))
    )
    (net (code "35") (name "LOAD2") (class "Default")
      (node (ref "JP2") (pin "18") (pinfunction "18_18") (pintype "passive"))
      (node (ref "Q30") (pin "1") (pinfunction "G_1") (pintype "bidirectional"))
    )
    (net (code "36") (name "LOAD3") (class "Default")
      (node (ref "JP2") (pin "19") (pinfunction "19_19") (pintype "passive"))
      (node (ref "Q146") (pin "1") (pinfunction "G_1") (pintype "bidirectional"))
    )
    (net (code "37") (name "NEXT0") (class "Default")
      (node (ref "JP2") (pin "12") (pinfunction "12_12") (pintype "passive"))
      (node (ref "Q110") (pin "1") (pinfunction "G_1") (pintype "bidirectional"))
    )
    (net (code "38") (name "NEXT1") (class "Default")
      (node (ref "JP2") (pin "13") (pinfunction "13_13") (pintype "passive"))
      (node (ref "Q77") (pin "1") (pinfunction "G_1") (pintype "bidirectional"))
    )
    (net (code "39") (name "NEXT2") (class "Default")
      (node (ref "JP2") (pin "14") (pinfunction "14_14") (pintype "passive"))
      (node (ref "Q27") (pin "1") (pinfunction "G_1") (pintype "bidirectional"))
    )
    (net (code "40") (name "NEXT3") (class "Default")
      (node (ref "JP2") (pin "15") (pinfunction "15_15") (pintype "passive"))
      (node (ref "Q143") (pin "1") (pinfunction "G_1") (pintype "bidirectional"))
    )
    (net (code "41") (name "Net-(JP2-Pad28)") (class "Default")
      (node (ref "JP2") (pin "28") (pinfunction "28_28") (pintype "passive"))
      (node (ref "LED1") (pin "A") (pinfunction "A_A") (pintype "passive"))
      (node (ref "LED2") (pin "A") (pinfunction "A_A") (pintype "passive"))
      (node (ref "LED3") (pin "A") (pinfunction "A_A") (pintype "passive"))
      (node (ref "LED4") (pin "A") (pinfunction "A_A") (pintype "passive"))
    )
    (net (code "42") (name "Net-(LED1-C)") (class "Default")
      (node (ref "LED1") (pin "K") (pinfunction "C_K") (pintype "passive"))
      (node (ref "R1") (pin "2") (pinfunction "2_2") (pintype "passive"))
    )
    (net (code "43") (name "Net-(LED2-C)") (class "Default")
      (node (ref "LED2") (pin "K") (pinfunction "C_K") (pintype "passive"))
      (node (ref "R2") (pin "2") (pinfunction "2_2") (pintype "passive"))
    )
    (net (code "44") (name "Net-(LED3-C)") (class "Default")
      (node (ref "LED3") (pin "K") (pinfunction "C_K") (pintype "passive"))
      (node (ref "R3") (pin "2") (pinfunction "2_2") (pintype "passive"))
    )
    (net (code "45") (name "Net-(LED4-C)") (class "Default")
      (node (ref "LED4") (pin "K") (pinfunction "C_K") (pintype "passive"))
      (node (ref "R4") (pin "2") (pinfunction "2_2") (pintype "passive"))
    )
    (net (code "46") (name "Net-(Q1-D)") (class "Default")
      (node (ref "Q1") (pin "3") (pinfunction "D_3") (pintype "bidirectional"))
      (node (ref "R1") (pin "1") (pinfunction "1_1") (pintype "passive"))
    )
    (net (code "47") (name "Net-(Q2-D)") (class "Default")
      (node (ref "Q2") (pin "3") (pinfunction "D_3") (pintype "bidirectional"))
      (node (ref "R2") (pin "1") (pinfunction "1_1") (pintype "passive"))
    )
    (net (code "48") (name "Net-(Q3-D)") (class "Default")
      (node (ref "Q3") (pin "3") (pinfunction "D_3") (pintype "bidirectional"))
      (node (ref "R3") (pin "1") (pinfunction "1_1") (pintype "passive"))
    )
    (net (code "49") (name "Net-(Q4-D)") (class "Default")
      (node (ref "Q4") (pin "3") (pinfunction "D_3") (pintype "bidirectional"))
      (node (ref "R4") (pin "1") (pinfunction "1_1") (pintype "passive"))
    )
    (net (code "50") (name "Net-(Q8-D)") (class "Default")
      (node (ref "Q8") (pin "3") (pinfunction "D_3") (pintype "bidirectional"))
      (node (ref "Q86") (pin "3") (pinfunction "D_3") (pintype "bidirectional"))
      (node (ref "Q90") (pin "1") (pinfunction "G_1") (pintype "bidirectional"))
      (node (ref "Q91") (pin "3") (pinfunction "D_3") (pintype "bidirectional"))
      (node (ref "Q93") (pin "1") (pinfunction "G_1") (pintype "bidirectional"))
      (node (ref "R36") (pin "1") (pinfunction "1_1") (pintype "passive"))
    )
    (net (code "51") (name "Net-(Q19-D)") (class "Default")
      (node (ref "Q19") (pin "3") (pinfunction "D_3") (pintype "bidirectional"))
      (node (ref "Q37") (pin "3") (pinfunction "D_3") (pintype "bidirectional"))
      (node (ref "Q41") (pin "1") (pinfunction "G_1") (pintype "bidirectional"))
      (node (ref "Q50") (pin "3") (pinfunction "D_3") (pintype "bidirectional"))
      (node (ref "Q52") (pin "1") (pinfunction "G_1") (pintype "bidirectional"))
      (node (ref "R14") (pin "1") (pinfunction "1_1") (pintype "passive"))
    )
    (net (code "52") (name "Net-(Q21-D)") (class "Default")
      (node (ref "Q21") (pin "3") (pinfunction "D_3") (pintype "bidirectional"))
      (node (ref "R9") (pin "1") (pinfunction "1_1") (pintype "passive"))
      (node (ref "SJ1") (pin "2") (pinfunction "2_2") (pintype "passive"))
    )
    (net (code "53") (name "Net-(Q35-D)") (class "Default")
      (node (ref "Q35") (pin "3") (pinfunction "D_3") (pintype "bidirectional"))
      (node (ref "Q36") (pin "3") (pinfunction "D_3") (pintype "bidirectional"))
      (node (ref "Q50") (pin "1") (pinfunction "G_1") (pintype "bidirectional"))
      (node (ref "R13") (pin "1") (pinfunction "1_1") (pintype "passive"))
    )
    (net (code "54") (name "Net-(Q37-G)") (class "Default")
      (node (ref "Q37") (pin "1") (pinfunction "G_1") (pintype "bidirectional"))
      (node (ref "Q40") (pin "3") (pinfunction "D_3") (pintype "bidirectional"))
      (node (ref "Q41") (pin "3") (pinfunction "D_3") (pintype "bidirectional"))
      (node (ref "Q55") (pin "1") (pinfunction "G_1") (pintype "bidirectional"))
      (node (ref "R16") (pin "1") (pinfunction "1_1") (pintype "passive"))
    )
    (net (code "55") (name "Net-(Q38-D)") (class "Default")
      (node (ref "Q38") (pin "3") (pinfunction "D_3") (pintype "bidirectional"))
      (node (ref "Q39") (pin "3") (pinfunction "D_3") (pintype "bidirectional"))
      (node (ref "Q40") (pin "1") (pinfunction "G_1") (pintype "bidirectional"))
      (node (ref "R15") (pin "1") (pinfunction "1_1") (pintype "passive"))
    )
    (net (code "56") (name "Net-(Q51-D)") (class "Default")
      (node (ref "Q51") (pin "3") (pinfunction "D_3") (pintype "bidirectional"))
      (node (ref "Q52") (pin "3") (pinfunction "D_3") (pintype "bidirectional"))
      (node (ref "Q66") (pin "1") (pinfunction "G_1") (pintype "bidirectional"))
      (node (ref "R17") (pin "1") (pinfunction "1_1") (pintype "passive"))
    )
    (net (code "57") (name "Net-(Q53-G)") (class "Default")
      (node (ref "Q53") (pin "1") (pinfunction "G_1") (pintype "bidirectional"))
      (node (ref "Q56") (pin "3") (pinfunction "D_3") (pintype "bidirectional"))
      (node (ref "Q57") (pin "3") (pinfunction "D_3") (pintype "bidirectional"))
      (node (ref "R24") (pin "1") (pinfunction "1_1") (pintype "passive"))
    )
    (net (code "58") (name "Net-(Q54-D)") (class "Default")
      (node (ref "Q54") (pin "3") (pinfunction "D_3") (pintype "bidirectional"))
      (node (ref "Q55") (pin "3") (pinfunction "D_3") (pintype "bidirectional"))
      (node (ref "Q56") (pin "1") (pinfunction "G_1") (pintype "bidirectional"))
      (node (ref "R23") (pin "1") (pinfunction "1_1") (pintype "passive"))
    )
    (net (code "59") (name "Net-(Q84-D)") (class "Default")
      (node (ref "Q84") (pin "3") (pinfunction "D_3") (pintype "bidirectional"))
      (node (ref "Q85") (pin "3") (pinfunction "D_3") (pintype "bidirectional"))
      (node (ref "Q91") (pin "1") (pinfunction "G_1") (pintype "bidirectional"))
      (node (ref "R35") (pin "1") (pinfunction "1_1") (pintype "passive"))
    )
    (net (code "60") (name "Net-(Q86-G)") (class "Default")
      (node (ref "Q86") (pin "1") (pinfunction "G_1") (pintype "bidirectional"))
      (node (ref "Q89") (pin "3") (pinfunction "D_3") (pintype "bidirectional"))
      (node (ref "Q90") (pin "3") (pinfunction "D_3") (pintype "bidirectional"))
      (node (ref "Q96") (pin "1") (pinfunction "G_1") (pintype "bidirectional"))
      (node (ref "R38") (pin "1") (pinfunction "1_1") (pintype "passive"))
    )
    (net (code "61") (name "Net-(Q87-D)") (class "Default")
      (node (ref "Q87") (pin "3") (pinfunction "D_3") (pintype "bidirectional"))
      (node (ref "Q88") (pin "3") (pinfunction "D_3") (pintype "bidirectional"))
      (node (ref "Q89") (pin "1") (pinfunction "G_1") (pintype "bidirectional"))
      (node (ref "R37") (pin "1") (pinfunction "1_1") (pintype "passive"))
    )
    (net (code "62") (name "Net-(Q92-D)") (class "Default")
      (node (ref "Q92") (pin "3") (pinfunction "D_3") (pintype "bidirectional"))
      (node (ref "Q93") (pin "3") (pinfunction "D_3") (pintype "bidirectional"))
      (node (ref "Q99") (pin "1") (pinfunction "G_1") (pintype "bidirectional"))
      (node (ref "R39") (pin "1") (pinfunction "1_1") (pintype "passive"))
    )
    (net (code "63") (name "Net-(Q94-G)") (class "Default")
      (node (ref "Q94") (pin "1") (pinfunction "G_1") (pintype "bidirectional"))
      (node (ref "Q97") (pin "3") (pinfunction "D_3") (pintype "bidirectional"))
      (node (ref "Q98") (pin "3") (pinfunction "D_3") (pintype "bidirectional"))
      (node (ref "R42") (pin "1") (pinfunction "1_1") (pintype "passive"))
    )
    (net (code "64") (name "Net-(Q95-D)") (class "Default")
      (node (ref "Q95") (pin "3") (pinfunction "D_3") (pintype "bidirectional"))
      (node (ref "Q96") (pin "3") (pinfunction "D_3") (pintype "bidirectional"))
      (node (ref "Q97") (pin "1") (pinfunction "G_1") (pintype "bidirectional"))
      (node (ref "R41") (pin "1") (pinfunction "1_1") (pintype "passive"))
    )
    (net (code "65") (name "Net-(Q117-D)") (class "Default")
      (node (ref "Q117") (pin "3") (pinfunction "D_3") (pintype "bidirectional"))
      (node (ref "Q118") (pin "3") (pinfunction "D_3") (pintype "bidirectional"))
      (node (ref "Q124") (pin "1") (pinfunction "G_1") (pintype "bidirectional"))
      (node (ref "R49") (pin "1") (pinfunction "1_1") (pintype "passive"))
    )
    (net (code "66") (name "Net-(Q119-D)") (class "Default")
      (node (ref "Q119") (pin "3") (pinfunction "D_3") (pintype "bidirectional"))
      (node (ref "Q123") (pin "1") (pinfunction "G_1") (pintype "bidirectional"))
      (node (ref "Q124") (pin "3") (pinfunction "D_3") (pintype "bidirectional"))
      (node (ref "Q126") (pin "1") (pinfunction "G_1") (pintype "bidirectional"))
      (node (ref "Q5") (pin "3") (pinfunction "D_3") (pintype "bidirectional"))
      (node (ref "R50") (pin "1") (pinfunction "1_1") (pintype "passive"))
    )
    (net (code "67") (name "Net-(Q119-G)") (class "Default")
      (node (ref "Q119") (pin "1") (pinfunction "G_1") (pintype "bidirectional"))
      (node (ref "Q122") (pin "3") (pinfunction "D_3") (pintype "bidirectional"))
      (node (ref "Q123") (pin "3") (pinfunction "D_3") (pintype "bidirectional"))
      (node (ref "Q129") (pin "1") (pinfunction "G_1") (pintype "bidirectional"))
      (node (ref "R52") (pin "1") (pinfunction "1_1") (pintype "passive"))
    )
    (net (code "68") (name "Net-(Q120-D)") (class "Default")
      (node (ref "Q120") (pin "3") (pinfunction "D_3") (pintype "bidirectional"))
      (node (ref "Q121") (pin "3") (pinfunction "D_3") (pintype "bidirectional"))
      (node (ref "Q122") (pin "1") (pinfunction "G_1") (pintype "bidirectional"))
      (node (ref "R51") (pin "1") (pinfunction "1_1") (pintype "passive"))
    )
    (net (code "69") (name "Net-(Q125-D)") (class "Default")
      (node (ref "Q125") (pin "3") (pinfunction "D_3") (pintype "bidirectional"))
      (node (ref "Q126") (pin "3") (pinfunction "D_3") (pintype "bidirectional"))
      (node (ref "Q132") (pin "1") (pinfunction "G_1") (pintype "bidirectional"))
      (node (ref "R53") (pin "1") (pinfunction "1_1") (pintype "passive"))
    )
    (net (code "70") (name "Net-(Q127-G)") (class "Default")
      (node (ref "Q127") (pin "1") (pinfunction "G_1") (pintype "bidirectional"))
      (node (ref "Q130") (pin "3") (pinfunction "D_3") (pintype "bidirectional"))
      (node (ref "Q131") (pin "3") (pinfunction "D_3") (pintype "bidirectional"))
      (node (ref "R56") (pin "1") (pinfunction "1_1") (pintype "passive"))
    )
    (net (code "71") (name "Net-(Q128-D)") (class "Default")
      (node (ref "Q128") (pin "3") (pinfunction "D_3") (pintype "bidirectional"))
      (node (ref "Q129") (pin "3") (pinfunction "D_3") (pintype "bidirectional"))
      (node (ref "Q130") (pin "1") (pinfunction "G_1") (pintype "bidirectional"))
      (node (ref "R55") (pin "1") (pinfunction "1_1") (pintype "passive"))
    )
    (net (code "72") (name "Net-(Q150-D)") (class "Default")
      (node (ref "Q150") (pin "3") (pinfunction "D_3") (pintype "bidirectional"))
      (node (ref "Q151") (pin "3") (pinfunction "D_3") (pintype "bidirectional"))
      (node (ref "Q157") (pin "1") (pinfunction "G_1") (pintype "bidirectional"))
      (node (ref "R63") (pin "1") (pinfunction "1_1") (pintype "passive"))
    )
    (net (code "73") (name "Net-(Q152-D)") (class "Default")
      (node (ref "Q152") (pin "3") (pinfunction "D_3") (pintype "bidirectional"))
      (node (ref "Q156") (pin "1") (pinfunction "G_1") (pintype "bidirectional"))
      (node (ref "Q157") (pin "3") (pinfunction "D_3") (pintype "bidirectional"))
      (node (ref "Q159") (pin "1") (pinfunction "G_1") (pintype "bidirectional"))
      (node (ref "Q18") (pin "3") (pinfunction "D_3") (pintype "bidirectional"))
      (node (ref "R64") (pin "1") (pinfunction "1_1") (pintype "passive"))
    )
    (net (code "74") (name "Net-(Q152-G)") (class "Default")
      (node (ref "Q152") (pin "1") (pinfunction "G_1") (pintype "bidirectional"))
      (node (ref "Q155") (pin "3") (pinfunction "D_3") (pintype "bidirectional"))
      (node (ref "Q156") (pin "3") (pinfunction "D_3") (pintype "bidirectional"))
      (node (ref "Q162") (pin "1") (pinfunction "G_1") (pintype "bidirectional"))
      (node (ref "R66") (pin "1") (pinfunction "1_1") (pintype "passive"))
    )
    (net (code "75") (name "Net-(Q153-D)") (class "Default")
      (node (ref "Q153") (pin "3") (pinfunction "D_3") (pintype "bidirectional"))
      (node (ref "Q154") (pin "3") (pinfunction "D_3") (pintype "bidirectional"))
      (node (ref "Q155") (pin "1") (pinfunction "G_1") (pintype "bidirectional"))
      (node (ref "R65") (pin "1") (pinfunction "1_1") (pintype "passive"))
    )
    (net (code "76") (name "Net-(Q158-D)") (class "Default")
      (node (ref "Q158") (pin "3") (pinfunction "D_3") (pintype "bidirectional"))
      (node (ref "Q159") (pin "3") (pinfunction "D_3") (pintype "bidirectional"))
      (node (ref "Q165") (pin "1") (pinfunction "G_1") (pintype "bidirectional"))
      (node (ref "R67") (pin "1") (pinfunction "1_1") (pintype "passive"))
    )
    (net (code "77") (name "Net-(Q160-G)") (class "Default")
      (node (ref "Q160") (pin "1") (pinfunction "G_1") (pintype "bidirectional"))
      (node (ref "Q163") (pin "3") (pinfunction "D_3") (pintype "bidirectional"))
      (node (ref "Q164") (pin "3") (pinfunction "D_3") (pintype "bidirectional"))
      (node (ref "R70") (pin "1") (pinfunction "1_1") (pintype "passive"))
    )
    (net (code "78") (name "Net-(Q161-D)") (class "Default")
      (node (ref "Q161") (pin "3") (pinfunction "D_3") (pintype "bidirectional"))
      (node (ref "Q162") (pin "3") (pinfunction "D_3") (pintype "bidirectional"))
      (node (ref "Q163") (pin "1") (pinfunction "G_1") (pintype "bidirectional"))
      (node (ref "R69") (pin "1") (pinfunction "1_1") (pintype "passive"))
    )
    (net (code "79") (name "OP1") (class "Default")
      (node (ref "JP2") (pin "2") (pinfunction "2_2") (pintype "passive"))
      (node (ref "Q106") (pin "1") (pinfunction "G_1") (pintype "bidirectional"))
      (node (ref "Q109") (pin "1") (pinfunction "G_1") (pintype "bidirectional"))
      (node (ref "Q139") (pin "1") (pinfunction "G_1") (pintype "bidirectional"))
      (node (ref "Q142") (pin "1") (pinfunction "G_1") (pintype "bidirectional"))
      (node (ref "Q15") (pin "1") (pinfunction "G_1") (pintype "bidirectional"))
      (node (ref "Q22") (pin "1") (pinfunction "G_1") (pintype "bidirectional"))
      (node (ref "Q26") (pin "1") (pinfunction "G_1") (pintype "bidirectional"))
      (node (ref "Q73") (pin "1") (pinfunction "G_1") (pintype "bidirectional"))
      (node (ref "Q76") (pin "1") (pinfunction "G_1") (pintype "bidirectional"))
    )
    (net (code "80") (name "OP2") (class "Default")
      (node (ref "JP2") (pin "3") (pinfunction "3_3") (pintype "passive"))
      (node (ref "Q105") (pin "1") (pinfunction "G_1") (pintype "bidirectional"))
      (node (ref "Q111") (pin "1") (pinfunction "G_1") (pintype "bidirectional"))
      (node (ref "Q138") (pin "1") (pinfunction "G_1") (pintype "bidirectional"))
      (node (ref "Q14") (pin "1") (pinfunction "G_1") (pintype "bidirectional"))
      (node (ref "Q144") (pin "1") (pinfunction "G_1") (pintype "bidirectional"))
      (node (ref "Q23") (pin "1") (pinfunction "G_1") (pintype "bidirectional"))
      (node (ref "Q28") (pin "1") (pinfunction "G_1") (pintype "bidirectional"))
      (node (ref "Q72") (pin "1") (pinfunction "G_1") (pintype "bidirectional"))
      (node (ref "Q78") (pin "1") (pinfunction "G_1") (pintype "bidirectional"))
    )
    (net (code "81") (name "OUT0") (class "Default")
      (node (ref "JP2") (pin "24") (pinfunction "24_24") (pintype "passive"))
      (node (ref "Q1") (pin "1") (pinfunction "G_1") (pintype "bidirectional"))
      (node (ref "Q127") (pin "3") (pinfunction "D_3") (pintype "bidirectional"))
      (node (ref "Q131") (pin "1") (pinfunction "G_1") (pintype "bidirectional"))
      (node (ref "Q132") (pin "3") (pinfunction "D_3") (pintype "bidirectional"))
      (node (ref "Q6") (pin "3") (pinfunction "D_3") (pintype "bidirectional"))
      (node (ref "R54") (pin "1") (pinfunction "1_1") (pintype "passive"))
    )
    (net (code "82") (name "OUT1") (class "Default")
      (node (ref "JP2") (pin "25") (pinfunction "25_25") (pintype "passive"))
      (node (ref "Q2") (pin "1") (pinfunction "G_1") (pintype "bidirectional"))
      (node (ref "Q7") (pin "3") (pinfunction "D_3") (pintype "bidirectional"))
      (node (ref "Q94") (pin "3") (pinfunction "D_3") (pintype "bidirectional"))
      (node (ref "Q98") (pin "1") (pinfunction "G_1") (pintype "bidirectional"))
      (node (ref "Q99") (pin "3") (pinfunction "D_3") (pintype "bidirectional"))
      (node (ref "R40") (pin "1") (pinfunction "1_1") (pintype "passive"))
    )
    (net (code "83") (name "OUT2") (class "Default")
      (node (ref "JP2") (pin "26") (pinfunction "26_26") (pintype "passive"))
      (node (ref "Q20") (pin "3") (pinfunction "D_3") (pintype "bidirectional"))
      (node (ref "Q3") (pin "1") (pinfunction "G_1") (pintype "bidirectional"))
      (node (ref "Q53") (pin "3") (pinfunction "D_3") (pintype "bidirectional"))
      (node (ref "Q57") (pin "1") (pinfunction "G_1") (pintype "bidirectional"))
      (node (ref "Q66") (pin "3") (pinfunction "D_3") (pintype "bidirectional"))
      (node (ref "R18") (pin "1") (pinfunction "1_1") (pintype "passive"))
    )
    (net (code "84") (name "OUT3") (class "Default")
      (node (ref "JP2") (pin "27") (pinfunction "27_27") (pintype "passive"))
      (node (ref "Q160") (pin "3") (pinfunction "D_3") (pintype "bidirectional"))
      (node (ref "Q164") (pin "1") (pinfunction "G_1") (pintype "bidirectional"))
      (node (ref "Q165") (pin "3") (pinfunction "D_3") (pintype "bidirectional"))
      (node (ref "Q17") (pin "3") (pinfunction "D_3") (pintype "bidirectional"))
      (node (ref "Q4") (pin "1") (pinfunction "G_1") (pintype "bidirectional"))
      (node (ref "R68") (pin "1") (pinfunction "1_1") (pintype "passive"))
    )
    (net (code "85") (name "PREV0") (class "Default")
      (node (ref "JP2") (pin "8") (pinfunction "8_8") (pintype "passive"))
      (node (ref "Q107") (pin "1") (pinfunction "G_1") (pintype "bidirectional"))
    )
    (net (code "86") (name "PREV1") (class "Default")
      (node (ref "JP2") (pin "9") (pinfunction "9_9") (pintype "passive"))
      (node (ref "Q74") (pin "1") (pinfunction "G_1") (pintype "bidirectional"))
    )
    (net (code "87") (name "PREV2") (class "Default")
      (node (ref "JP2") (pin "10") (pinfunction "10_10") (pintype "passive"))
      (node (ref "Q16") (pin "1") (pinfunction "G_1") (pintype "bidirectional"))
    )
    (net (code "88") (name "PREV3") (class "Default")
      (node (ref "JP2") (pin "11") (pinfunction "11_11") (pintype "passive"))
      (node (ref "Q140") (pin "1") (pinfunction "G_1") (pintype "bidirectional"))
    )
    (net (code "89") (name "VCC") (class "Default")
      (node (ref "C1") (pin "1") (pinfunction "1_1") (pintype "passive"))
      (node (ref "C2") (pin "1") (pinfunction "1_1") (pintype "passive"))
      (node (ref "C3") (pin "1") (pinfunction "1_1") (pintype "passive"))
      (node (ref "C4") (pin "1") (pinfunction "1_1") (pintype "passive"))
      (node (ref "C5") (pin "1") (pinfunction "1_1") (pintype "passive"))
      (node (ref "JP2") (pin "29") (pinfunction "29_29") (pintype "passive"))
      (node (ref "R10") (pin "2") (pinfunction "2_2") (pintype "passive"))
      (node (ref "R11") (pin "1") (pinfunction "1_1") (pintype "passive"))
      (node (ref "R12") (pin "1") (pinfunction "1_1") (pintype "passive"))
      (node (ref "R13") (pin "2") (pinfunction "2_2") (pintype "passive"))
      (node (ref "R14") (pin "2") (pinfunction "2_2") (pintype "passive"))
      (node (ref "R15") (pin "2") (pinfunction "2_2") (pintype "passive"))
      (node (ref "R16") (pin "2") (pinfunction "2_2") (pintype "passive"))
      (node (ref "R17") (pin "2") (pinfunction "2_2") (pintype "passive"))
      (node (ref "R18") (pin "2") (pinfunction "2_2") (pintype "passive"))
      (node (ref "R19") (pin "2") (pinfunction "2_2") (pintype "passive"))
      (node (ref "R23") (pin "2") (pinfunction "2_2") (pintype "passive"))
      (node (ref "R24") (pin "2") (pinfunction "2_2") (pintype "passive"))
      (node (ref "R25") (pin "1") (pinfunction "1_1") (pintype "passive"))
      (node (ref "R26") (pin "1") (pinfunction "1_1") (pintype "passive"))
      (node (ref "R31") (pin "1") (pinfunction "1_1") (pintype "passive"))
      (node (ref "R32") (pin "1") (pinfunction "1_1") (pintype "passive"))
      (node (ref "R33") (pin "1") (pinfunction "1_1") (pintype "passive"))
      (node (ref "R34") (pin "1") (pinfunction "1_1") (pintype "passive"))
      (node (ref "R35") (pin "2") (pinfunction "2_2") (pintype "passive"))
      (node (ref "R36") (pin "2") (pinfunction "2_2") (pintype "passive"))
      (node (ref "R37") (pin "2") (pinfunction "2_2") (pintype "passive"))
      (node (ref "R38") (pin "2") (pinfunction "2_2") (pintype "passive"))
      (node (ref "R39") (pin "2") (pinfunction "2_2") (pintype "passive"))
      (node (ref "R40") (pin "2") (pinfunction "2_2") (pintype "passive"))
      (node (ref "R41") (pin "2") (pinfunction "2_2") (pintype "passive"))
      (node (ref "R42") (pin "2") (pinfunction "2_2") (pintype "passive"))
      (node (ref "R43") (pin "1") (pinfunction "1_1") (pintype "passive"))
      (node (ref "R44") (pin "1") (pinfunction "1_1") (pintype "passive"))
      (node (ref "R45") (pin "1") (pinfunction "1_1") (pintype "passive"))
      (node (ref "R46") (pin "1") (pinfunction "1_1") (pintype "passive"))
      (node (ref "R47") (pin "1") (pinfunction "1_1") (pintype "passive"))
      (node (ref "R48") (pin "1") (pinfunction "1_1") (pintype "passive"))
      (node (ref "R49") (pin "2") (pinfunction "2_2") (pintype "passive"))
      (node (ref "R5") (pin "1") (pinfunction "1_1") (pintype "passive"))
      (node (ref "R50") (pin "2") (pinfunction "2_2") (pintype "passive"))
      (node (ref "R51") (pin "2") (pinfunction "2_2") (pintype "passive"))
      (node (ref "R52") (pin "2") (pinfunction "2_2") (pintype "passive"))
      (node (ref "R53") (pin "2") (pinfunction "2_2") (pintype "passive"))
      (node (ref "R54") (pin "2") (pinfunction "2_2") (pintype "passive"))
      (node (ref "R55") (pin "2") (pinfunction "2_2") (pintype "passive"))
      (node (ref "R56") (pin "2") (pinfunction "2_2") (pintype "passive"))
      (node (ref "R57") (pin "1") (pinfunction "1_1") (pintype "passive"))
      (node (ref "R58") (pin "1") (pinfunction "1_1") (pintype "passive"))
      (node (ref "R59") (pin "1") (pinfunction "1_1") (pintype "passive"))
      (node (ref "R6") (pin "1") (pinfunction "1_1") (pintype "passive"))
      (node (ref "R60") (pin "1") (pinfunction "1_1") (pintype "passive"))
      (node (ref "R61") (pin "1") (pinfunction "1_1") (pintype "passive"))
      (node (ref "R62") (pin "1") (pinfunction "1_1") (pintype "passive"))
      (node (ref "R63") (pin "2") (pinfunction "2_2") (pintype "passive"))
      (node (ref "R64") (pin "2") (pinfunction "2_2") (pintype "passive"))
      (node (ref "R65") (pin "2") (pinfunction "2_2") (pintype "passive"))
      (node (ref "R66") (pin "2") (pinfunction "2_2") (pintype "passive"))
      (node (ref "R67") (pin "2") (pinfunction "2_2") (pintype "passive"))
      (node (ref "R68") (pin "2") (pinfunction "2_2") (pintype "passive"))
      (node (ref "R69") (pin "2") (pinfunction "2_2") (pintype "passive"))
      (node (ref "R7") (pin "1") (pinfunction "1_1") (pintype "passive"))
      (node (ref "R70") (pin "2") (pinfunction "2_2") (pintype "passive"))
      (node (ref "R8") (pin "1") (pinfunction "1_1") (pintype "passive"))
      (node (ref "R9") (pin "2") (pinfunction "2_2") (pintype "passive"))
    )
    (net (code "90") (name "unconnected-(JP2-Pad5)") (class "Default")
      (node (ref "JP2") (pin "5") (pinfunction "5_5") (pintype "passive"))
    )
    (net (code "91") (name "unconnected-(JP2-Pad6)") (class "Default")
      (node (ref "JP2") (pin "6") (pinfunction "6_6") (pintype "passive"))
    )
    (net (code "92") (name "unconnected-(JP2-Pad7)") (class "Default")
      (node (ref "JP2") (pin "7") (pinfunction "7_7") (pintype "passive"))
    )
    (net (code "93") (name "{slash}CLK") (class "Default")
      (node (ref "Q117") (pin "1") (pinfunction "G_1") (pintype "bidirectional"))
      (node (ref "Q120") (pin "1") (pinfunction "G_1") (pintype "bidirectional"))
      (node (ref "Q150") (pin "1") (pinfunction "G_1") (pintype "bidirectional"))
      (node (ref "Q153") (pin "1") (pinfunction "G_1") (pintype "bidirectional"))
      (node (ref "Q35") (pin "1") (pinfunction "G_1") (pintype "bidirectional"))
      (node (ref "Q38") (pin "1") (pinfunction "G_1") (pintype "bidirectional"))
      (node (ref "Q84") (pin "1") (pinfunction "G_1") (pintype "bidirectional"))
      (node (ref "Q87") (pin "1") (pinfunction "G_1") (pintype "bidirectional"))
      (node (ref "SJ1") (pin "3") (pinfunction "3_3") (pintype "passive"))
      (node (ref "SJ2") (pin "3") (pinfunction "3_3") (pintype "passive"))
    )
    (net (code "94") (name "{slash}OP1") (class "Default")
      (node (ref "Q112") (pin "1") (pinfunction "G_1") (pintype "bidirectional"))
      (node (ref "Q115") (pin "1") (pinfunction "G_1") (pintype "bidirectional"))
      (node (ref "Q145") (pin "1") (pinfunction "G_1") (pintype "bidirectional"))
      (node (ref "Q148") (pin "1") (pinfunction "G_1") (pintype "bidirectional"))
      (node (ref "Q22") (pin "3") (pinfunction "D_3") (pintype "bidirectional"))
      (node (ref "Q29") (pin "1") (pinfunction "G_1") (pintype "bidirectional"))
      (node (ref "Q32") (pin "1") (pinfunction "G_1") (pintype "bidirectional"))
      (node (ref "Q79") (pin "1") (pinfunction "G_1") (pintype "bidirectional"))
      (node (ref "Q82") (pin "1") (pinfunction "G_1") (pintype "bidirectional"))
      (node (ref "R10") (pin "1") (pinfunction "1_1") (pintype "passive"))
    )
    (net (code "95") (name "{slash}OP2") (class "Default")
      (node (ref "Q108") (pin "1") (pinfunction "G_1") (pintype "bidirectional"))
      (node (ref "Q114") (pin "1") (pinfunction "G_1") (pintype "bidirectional"))
      (node (ref "Q141") (pin "1") (pinfunction "G_1") (pintype "bidirectional"))
      (node (ref "Q147") (pin "1") (pinfunction "G_1") (pintype "bidirectional"))
      (node (ref "Q23") (pin "3") (pinfunction "D_3") (pintype "bidirectional"))
      (node (ref "Q25") (pin "1") (pinfunction "G_1") (pintype "bidirectional"))
      (node (ref "Q31") (pin "1") (pinfunction "G_1") (pintype "bidirectional"))
      (node (ref "Q75") (pin "1") (pinfunction "G_1") (pintype "bidirectional"))
      (node (ref "Q81") (pin "1") (pinfunction "G_1") (pintype "bidirectional"))
      (node (ref "R19") (pin "1") (pinfunction "1_1") (pintype "passive"))
    )
  )
)
